# biofeedback_2560_3V.net
KiCad netlist of a schematic drawn in EAGLE
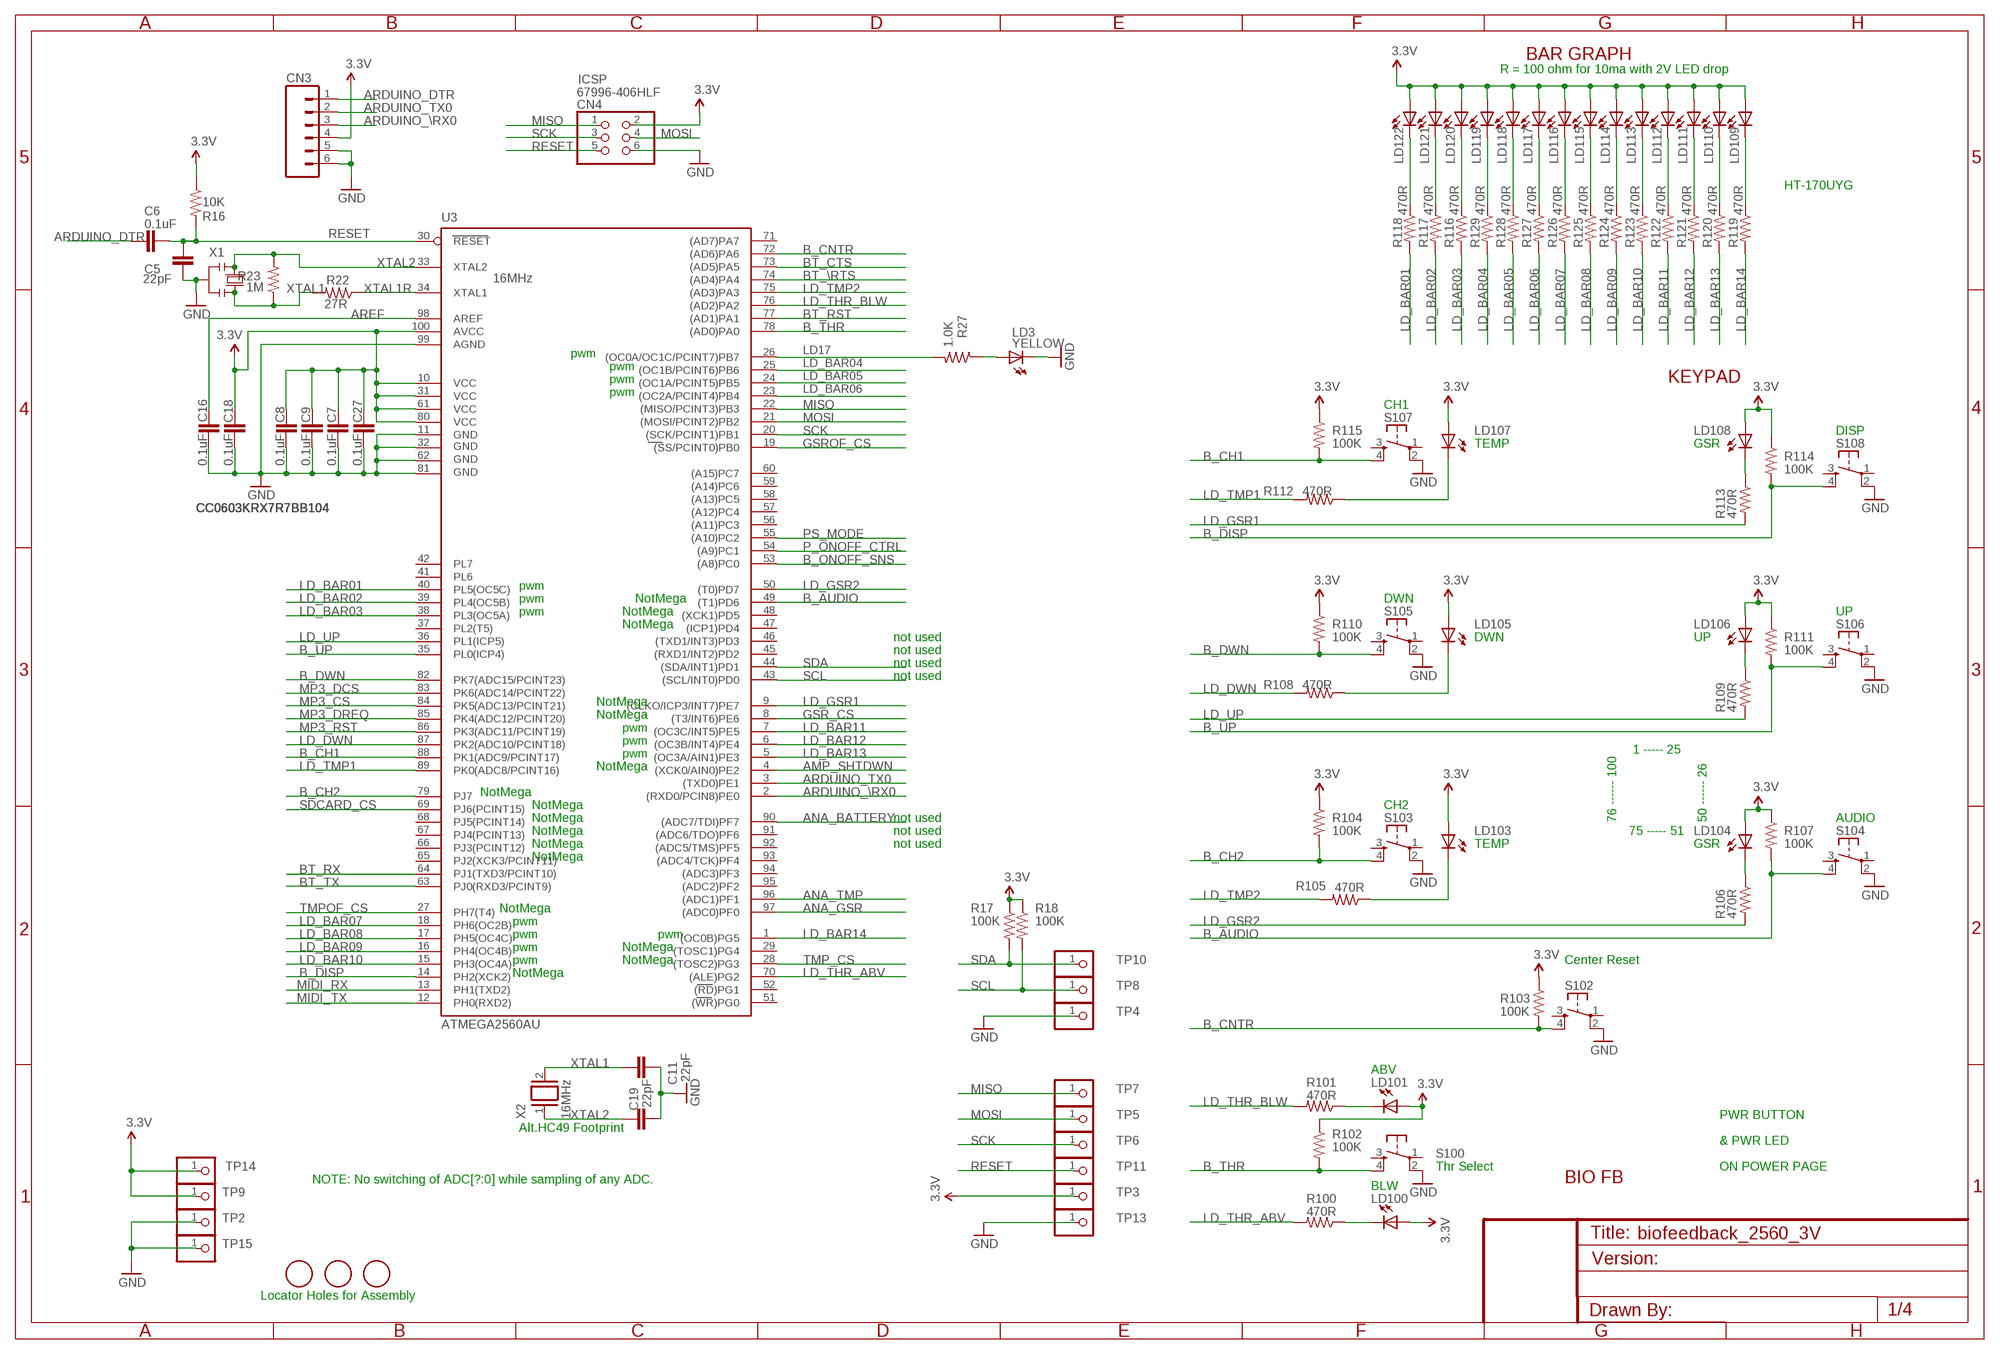
[diagram p0: schematic, sheet 1]
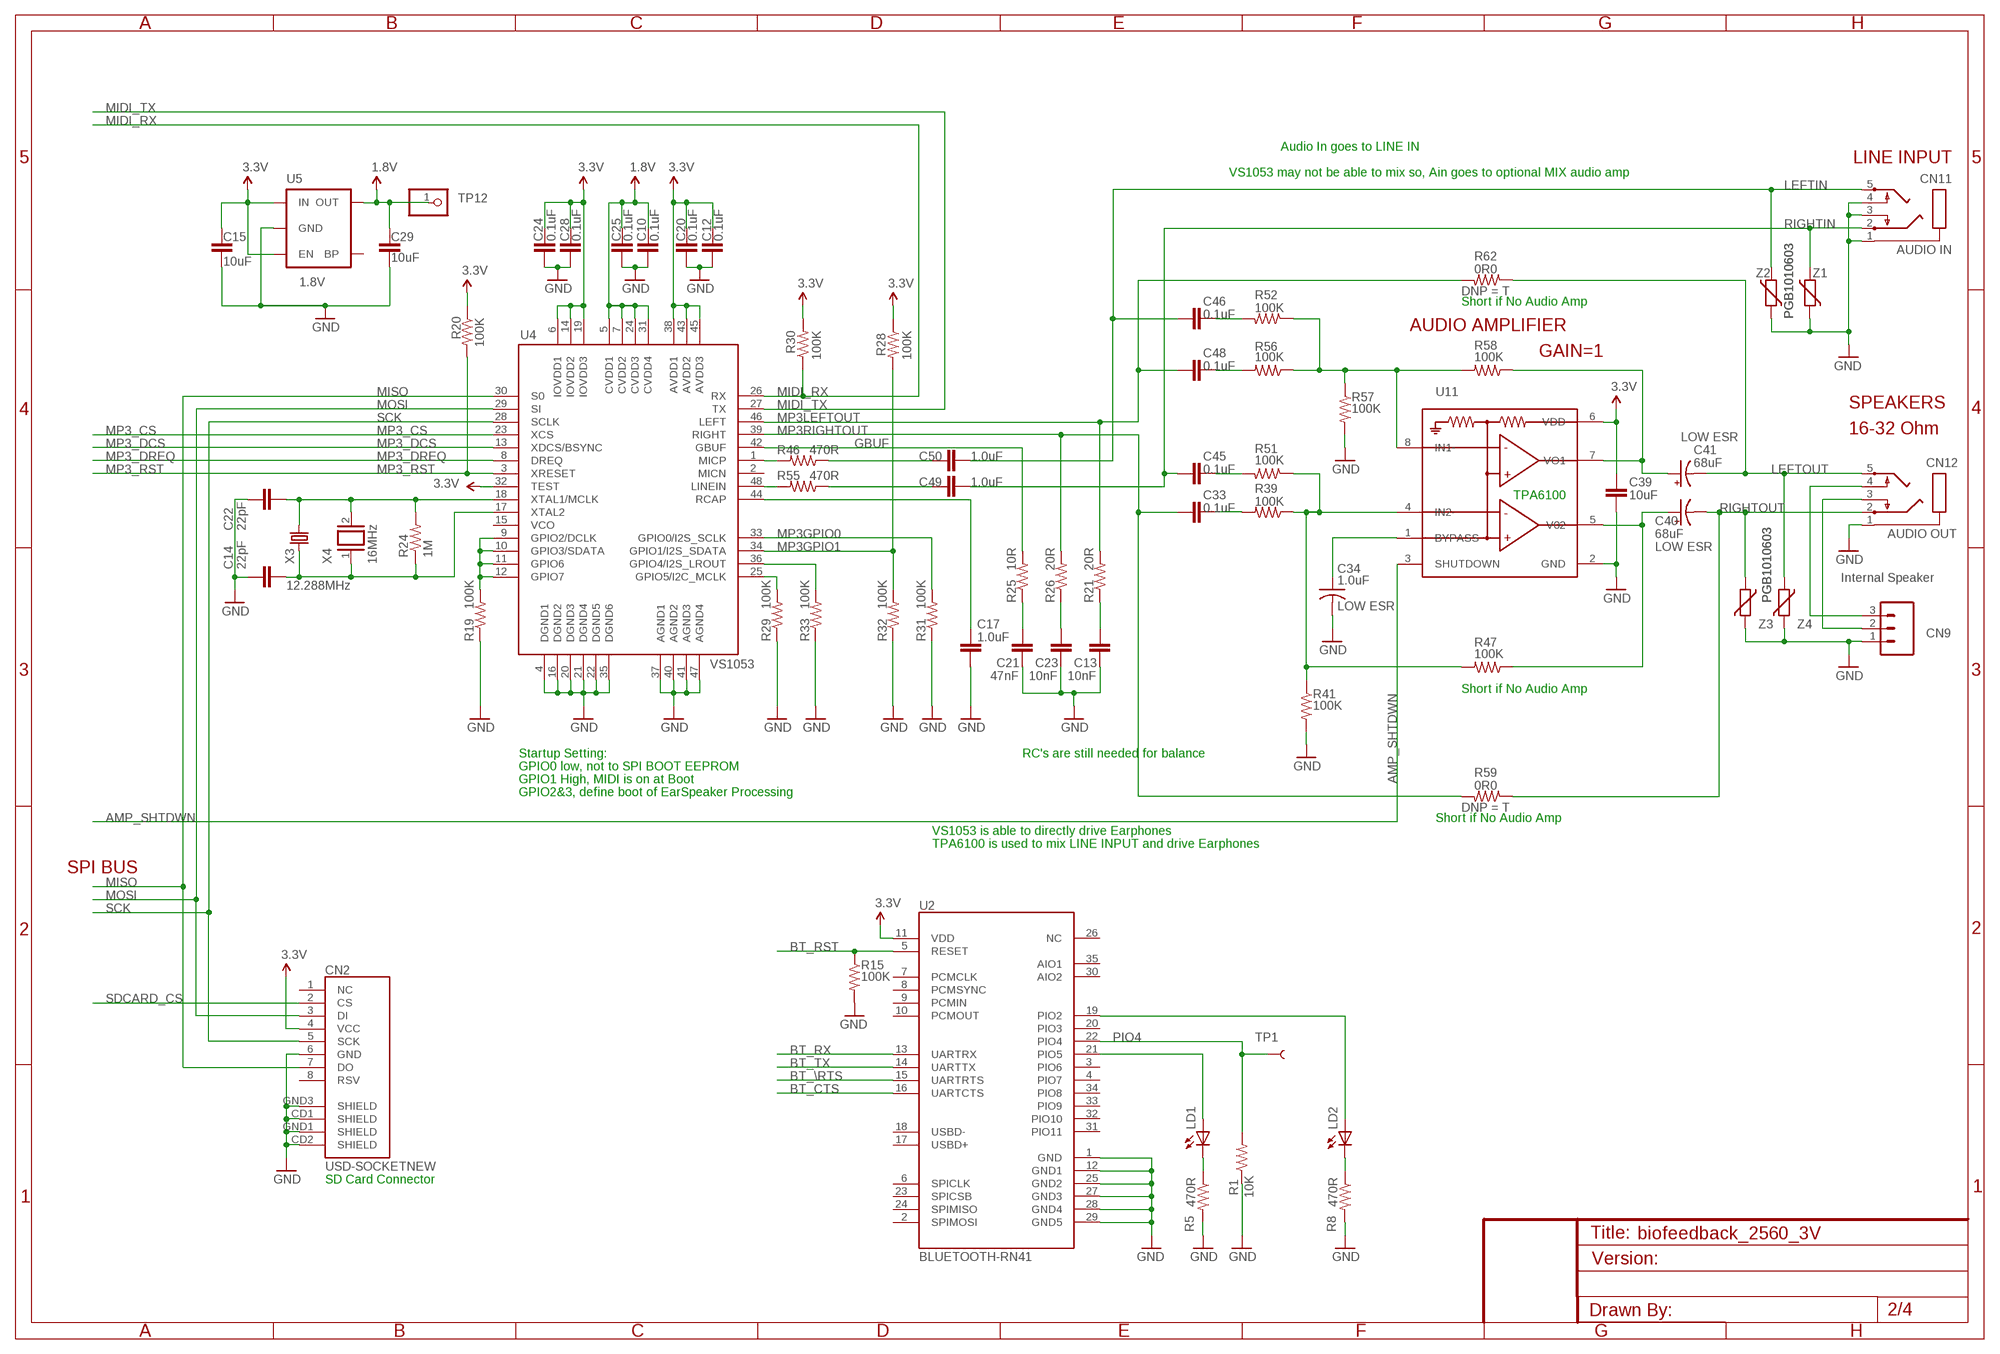
[diagram p1: schematic, sheet 2]
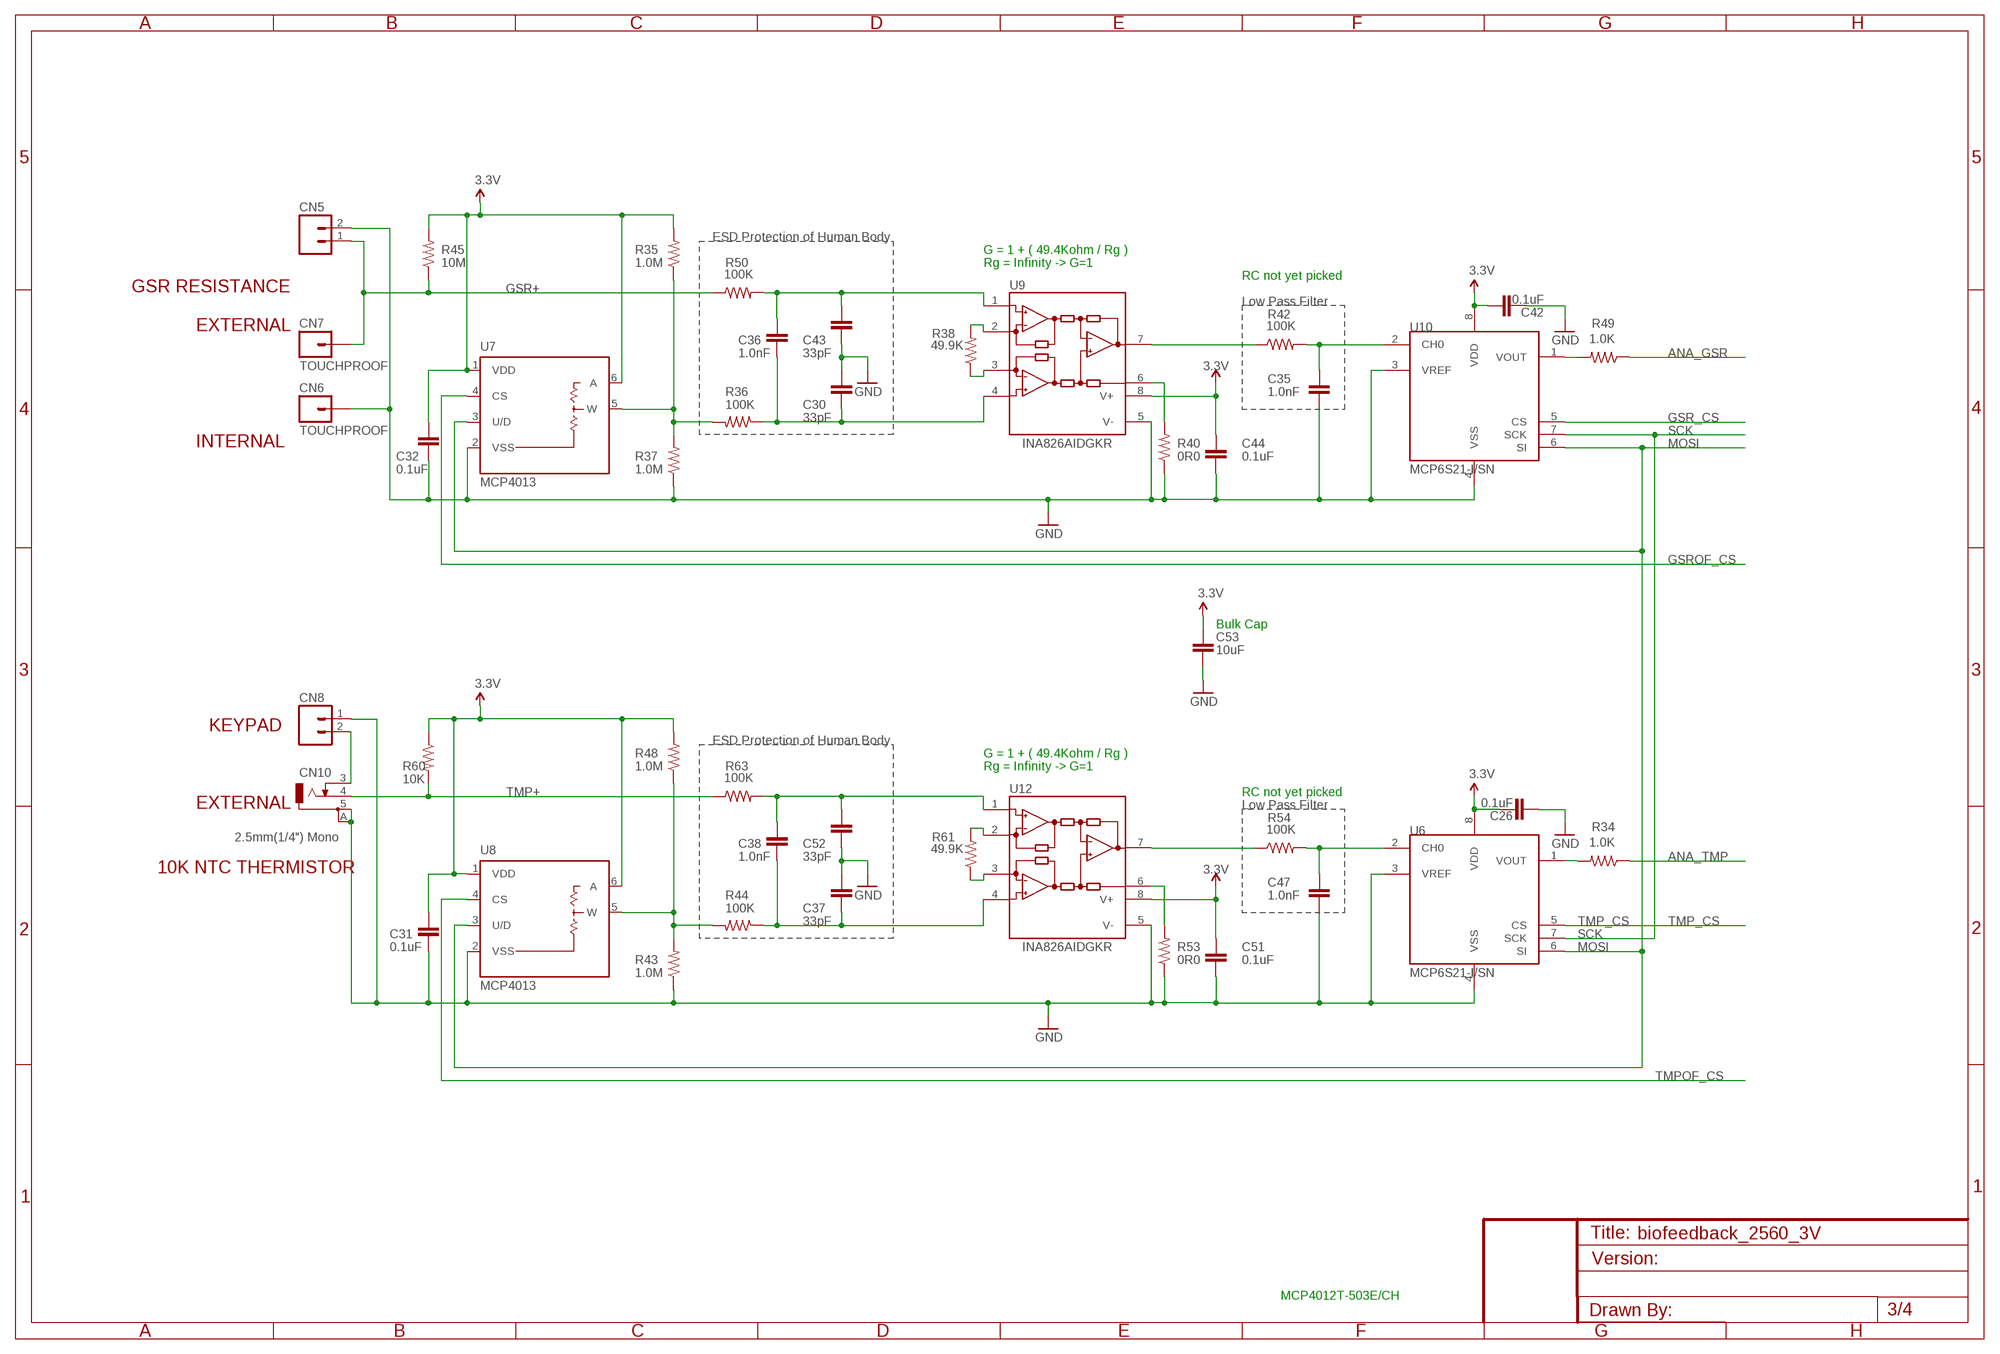
[diagram p2: schematic, sheet 3]
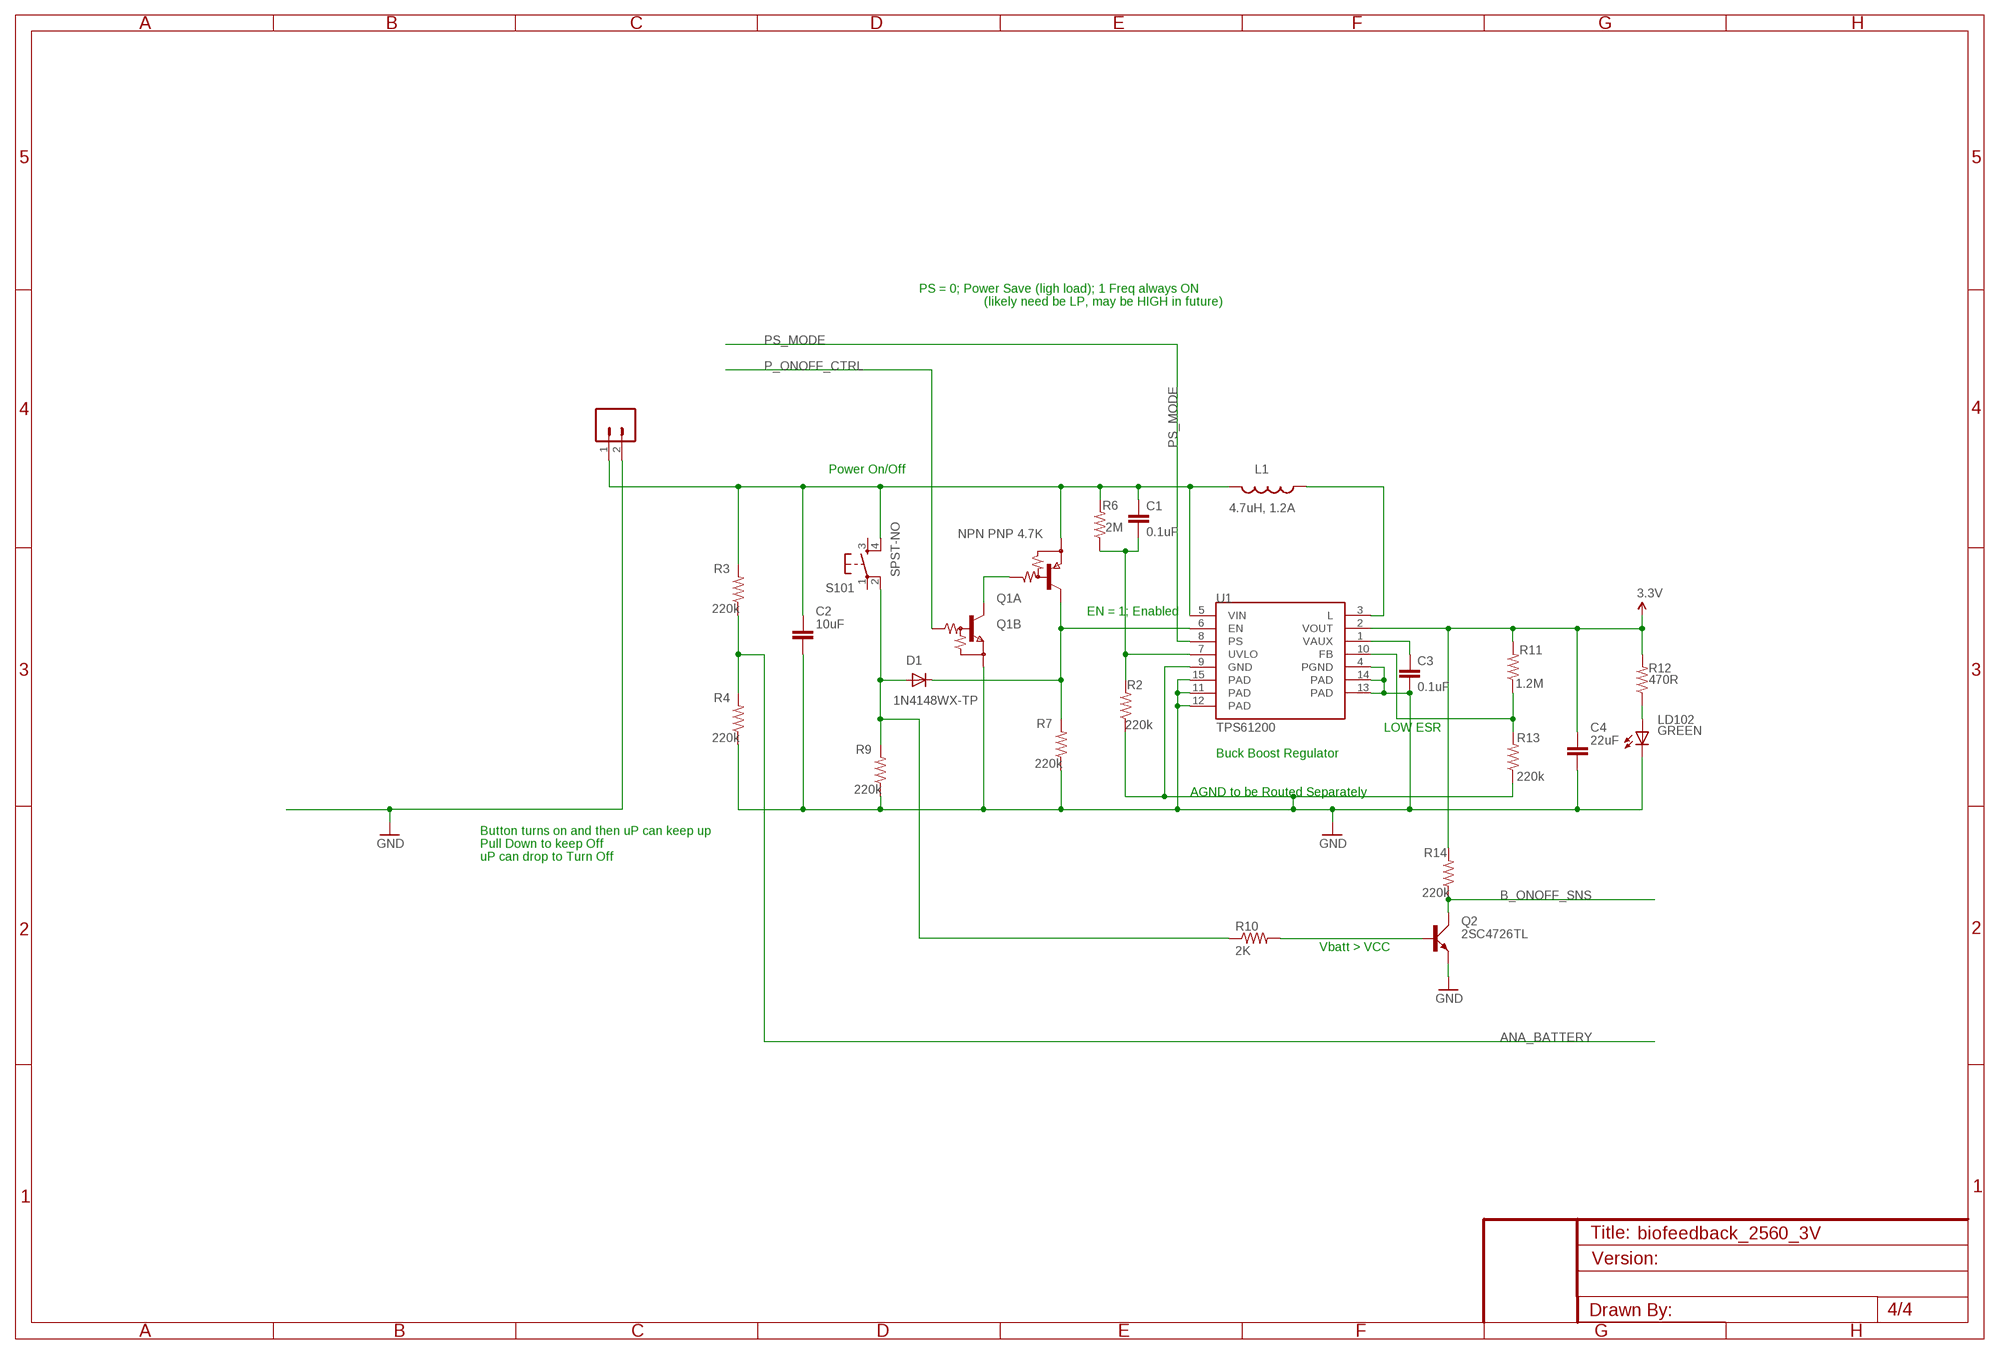
[diagram p3: schematic, sheet 4]

(export (version "E")
  (design (tool "Eeschema 10.0.6"))
  (components
    (comp (ref "C5")
      (value "22pF")
      (footprint "eagle-import:C0603")
      (fields (field (name "PARTNO") "GRM0335C1E220JD01D"))
      (libsource (lib "eagle-import") (part "resistor_C-EUC0603"))
    )
    (comp (ref "C6")
      (value "0.1uF")
      (footprint "eagle-import:C0603")
      (fields (field (name "PARTNO") "CC0603KRX7R7BB104"))
      (libsource (lib "eagle-import") (part "resistor_C-EUC0603"))
    )
    (comp (ref "C7")
      (value "0.1uF")
      (footprint "eagle-import:C0603")
      (fields (field (name "PARTNO") "CC0603KRX7R7BB104"))
      (libsource (lib "eagle-import") (part "resistor_C-EUC0603"))
    )
    (comp (ref "C8")
      (value "0.1uF")
      (footprint "eagle-import:C0603")
      (fields (field (name "PARTNO") "CC0603KRX7R7BB104"))
      (libsource (lib "eagle-import") (part "resistor_C-EUC0603"))
    )
    (comp (ref "C9")
      (value "0.1uF")
      (footprint "eagle-import:C0603")
      (fields (field (name "PARTNO") "CC0603KRX7R7BB104"))
      (libsource (lib "eagle-import") (part "resistor_C-EUC0603"))
    )
    (comp (ref "C11")
      (value "22pF")
      (footprint "eagle-import:C0603")
      (fields (field (name "PARTNO") "GRM0335C1E220JD01D"))
      (libsource (lib "eagle-import") (part "resistor_C-EUC0603"))
    )
    (comp (ref "C16")
      (value "0.1uF")
      (footprint "eagle-import:C0603")
      (fields (field (name "PARTNO") "CC0603KRX7R7BB104"))
      (libsource (lib "eagle-import") (part "resistor_C-EUC0603"))
    )
    (comp (ref "C18")
      (value "0.1uF")
      (footprint "eagle-import:C0603")
      (fields (field (name "PARTNO") "CC0603KRX7R7BB104"))
      (libsource (lib "eagle-import") (part "resistor_C-EUC0603"))
    )
    (comp (ref "C19")
      (value "22pF")
      (footprint "eagle-import:C0603")
      (fields (field (name "PARTNO") "GRM0335C1E220JD01D"))
      (libsource (lib "eagle-import") (part "resistor_C-EUC0603"))
    )
    (comp (ref "C27")
      (value "0.1uF")
      (footprint "eagle-import:C0603")
      (fields (field (name "PARTNO") "CC0603KRX7R7BB104"))
      (libsource (lib "eagle-import") (part "resistor_C-EUC0603"))
    )
    (comp (ref "CN3")
      (value "NSTUFF")
      (footprint "eagle-import:1X06")
      (fields (field (name "PARTNO") "640456-6"))
      (libsource (lib "eagle-import") (part "M06SIP"))
    )
    (comp (ref "CN4")
      (value "ICSP")
      (footprint "eagle-import:2X03")
      (fields (field (name "PARTNO") "67996-406HLF"))
      (libsource (lib "eagle-import") (part "PINHD-2X3"))
    )
    (comp (ref "LD3")
      (value "YELLOW")
      (footprint "eagle-import:CHIP-LED0805")
      (fields (field (name "PARTNO") "APT2012YC"))
      (libsource (lib "eagle-import") (part "LEDCHIP-LED0805"))
    )
    (comp (ref "LD100")
      (value "GREEN")
      (footprint "eagle-import:CHIP-LED0805")
      (fields (field (name "PARTNO") "LG R971-KN-1-0-20-R18"))
      (libsource (lib "eagle-import") (part "LEDCHIP-LED0805"))
    )
    (comp (ref "LD101")
      (value "GREEN")
      (footprint "eagle-import:CHIP-LED0805")
      (fields (field (name "PARTNO") "LG R971-KN-1-0-20-R18"))
      (libsource (lib "eagle-import") (part "LEDCHIP-LED0805"))
    )
    (comp (ref "LD103")
      (value "GREEN")
      (footprint "eagle-import:CHIP-LED0805")
      (fields (field (name "PARTNO") "LG R971-KN-1-0-20-R18"))
      (libsource (lib "eagle-import") (part "LEDCHIP-LED0805"))
    )
    (comp (ref "LD104")
      (value "GREEN")
      (footprint "eagle-import:CHIP-LED0805")
      (fields (field (name "PARTNO") "LG R971-KN-1-0-20-R18"))
      (libsource (lib "eagle-import") (part "LEDCHIP-LED0805"))
    )
    (comp (ref "LD105")
      (value "GREEN")
      (footprint "eagle-import:CHIP-LED0805")
      (fields (field (name "PARTNO") "LG R971-KN-1-0-20-R18"))
      (libsource (lib "eagle-import") (part "LEDCHIP-LED0805"))
    )
    (comp (ref "LD106")
      (value "GREEN")
      (footprint "eagle-import:CHIP-LED0805")
      (fields (field (name "PARTNO") "LG R971-KN-1-0-20-R18"))
      (libsource (lib "eagle-import") (part "LEDCHIP-LED0805"))
    )
    (comp (ref "LD107")
      (value "GREEN")
      (footprint "eagle-import:CHIP-LED0805")
      (fields (field (name "PARTNO") "LG R971-KN-1-0-20-R18"))
      (libsource (lib "eagle-import") (part "LEDCHIP-LED0805"))
    )
    (comp (ref "LD108")
      (value "GREEN")
      (footprint "eagle-import:CHIP-LED0805")
      (fields (field (name "PARTNO") "LG R971-KN-1-0-20-R18"))
      (libsource (lib "eagle-import") (part "LEDCHIP-LED0805"))
    )
    (comp (ref "LD109")
      (value "GREEN")
      (footprint "eagle-import:CHIP-LED0805")
      (fields (field (name "PARTNO") "LG R971-KN-1-0-20-R18"))
      (libsource (lib "eagle-import") (part "LEDCHIP-LED0805"))
    )
    (comp (ref "LD110")
      (value "GREEN")
      (footprint "eagle-import:CHIP-LED0805")
      (fields (field (name "PARTNO") "LG R971-KN-1-0-20-R18"))
      (libsource (lib "eagle-import") (part "LEDCHIP-LED0805"))
    )
    (comp (ref "LD111")
      (value "GREEN")
      (footprint "eagle-import:CHIP-LED0805")
      (fields (field (name "PARTNO") "LG R971-KN-1-0-20-R18"))
      (libsource (lib "eagle-import") (part "LEDCHIP-LED0805"))
    )
    (comp (ref "LD112")
      (value "GREEN")
      (footprint "eagle-import:CHIP-LED0805")
      (fields (field (name "PARTNO") "LG R971-KN-1-0-20-R18"))
      (libsource (lib "eagle-import") (part "LEDCHIP-LED0805"))
    )
    (comp (ref "LD113")
      (value "GREEN")
      (footprint "eagle-import:CHIP-LED0805")
      (fields (field (name "PARTNO") "LG R971-KN-1-0-20-R18"))
      (libsource (lib "eagle-import") (part "LEDCHIP-LED0805"))
    )
    (comp (ref "LD114")
      (value "GREEN")
      (footprint "eagle-import:CHIP-LED0805")
      (fields (field (name "PARTNO") "LG R971-KN-1-0-20-R18"))
      (libsource (lib "eagle-import") (part "LEDCHIP-LED0805"))
    )
    (comp (ref "LD115")
      (value "GREEN")
      (footprint "eagle-import:CHIP-LED0805")
      (fields (field (name "PARTNO") "LG R971-KN-1-0-20-R18"))
      (libsource (lib "eagle-import") (part "LEDCHIP-LED0805"))
    )
    (comp (ref "LD116")
      (value "GREEN")
      (footprint "eagle-import:CHIP-LED0805")
      (fields (field (name "PARTNO") "LG R971-KN-1-0-20-R18"))
      (libsource (lib "eagle-import") (part "LEDCHIP-LED0805"))
    )
    (comp (ref "LD117")
      (value "GREEN")
      (footprint "eagle-import:CHIP-LED0805")
      (fields (field (name "PARTNO") "LG R971-KN-1-0-20-R18"))
      (libsource (lib "eagle-import") (part "LEDCHIP-LED0805"))
    )
    (comp (ref "LD118")
      (value "GREEN")
      (footprint "eagle-import:CHIP-LED0805")
      (fields (field (name "PARTNO") "LG R971-KN-1-0-20-R18"))
      (libsource (lib "eagle-import") (part "LEDCHIP-LED0805"))
    )
    (comp (ref "LD119")
      (value "GREEN")
      (footprint "eagle-import:CHIP-LED0805")
      (fields (field (name "PARTNO") "LG R971-KN-1-0-20-R18"))
      (libsource (lib "eagle-import") (part "LEDCHIP-LED0805"))
    )
    (comp (ref "LD120")
      (value "GREEN")
      (footprint "eagle-import:CHIP-LED0805")
      (fields (field (name "PARTNO") "LG R971-KN-1-0-20-R18"))
      (libsource (lib "eagle-import") (part "LEDCHIP-LED0805"))
    )
    (comp (ref "LD121")
      (value "GREEN")
      (footprint "eagle-import:CHIP-LED0805")
      (fields (field (name "PARTNO") "LG R971-KN-1-0-20-R18"))
      (libsource (lib "eagle-import") (part "LEDCHIP-LED0805"))
    )
    (comp (ref "LD122")
      (value "GREEN")
      (footprint "eagle-import:CHIP-LED0805")
      (fields (field (name "PARTNO") "LG R971-KN-1-0-20-R18"))
      (libsource (lib "eagle-import") (part "LEDCHIP-LED0805"))
    )
    (comp (ref "MN1")
      (value "FIDUCIALMOUNT")
      (footprint "eagle-import:FIDUCIA-MOUNT")
      (libsource (lib "eagle-import") (part "FIDUCIALMOUNT"))
    )
    (comp (ref "MN2")
      (value "FIDUCIALMOUNT")
      (footprint "eagle-import:FIDUCIA-MOUNT")
      (libsource (lib "eagle-import") (part "FIDUCIALMOUNT"))
    )
    (comp (ref "MN3")
      (value "FIDUCIALMOUNT")
      (footprint "eagle-import:FIDUCIA-MOUNT")
      (libsource (lib "eagle-import") (part "FIDUCIALMOUNT"))
    )
    (comp (ref "R16")
      (value "10K")
      (footprint "eagle-import:R0603")
      (fields (field (name "PARTNO") "RC0603JR-0710KL"))
      (libsource (lib "eagle-import") (part "R-US_R0603"))
    )
    (comp (ref "R17")
      (value "100K")
      (footprint "eagle-import:R0603")
      (fields (field (name "PARTNO") "RC0603JR-07100KL"))
      (libsource (lib "eagle-import") (part "R-US_R0603"))
    )
    (comp (ref "R18")
      (value "100K")
      (footprint "eagle-import:R0603")
      (fields (field (name "PARTNO") "RC0603JR-07100KL"))
      (libsource (lib "eagle-import") (part "R-US_R0603"))
    )
    (comp (ref "R22")
      (value "27R")
      (footprint "eagle-import:R0603")
      (fields (field (name "PARTNO") "ERJ-3EKF27R0V"))
      (libsource (lib "eagle-import") (part "R-US_R0603"))
    )
    (comp (ref "R23")
      (value "1M")
      (footprint "eagle-import:R0603")
      (fields (field (name "PARTNO") "RC0603JR-071ML"))
      (libsource (lib "eagle-import") (part "R-US_R0603"))
    )
    (comp (ref "R27")
      (value "1.0K")
      (footprint "eagle-import:R0603")
      (fields (field (name "PARTNO") "RC0603JR-071KL"))
      (libsource (lib "eagle-import") (part "R-US_R0603"))
    )
    (comp (ref "R100")
      (value "470R")
      (footprint "eagle-import:R0603")
      (fields (field (name "PARTNO") "RC0603JR-07470RL"))
      (libsource (lib "eagle-import") (part "R-US_R0603"))
    )
    (comp (ref "R101")
      (value "470R")
      (footprint "eagle-import:R0603")
      (fields (field (name "PARTNO") "RC0603JR-07470RL"))
      (libsource (lib "eagle-import") (part "R-US_R0603"))
    )
    (comp (ref "R102")
      (value "100K")
      (footprint "eagle-import:R0603")
      (fields (field (name "PARTNO") "RC0603JR-07100KL"))
      (libsource (lib "eagle-import") (part "R-US_R0603"))
    )
    (comp (ref "R103")
      (value "100K")
      (footprint "eagle-import:R0603")
      (fields (field (name "PARTNO") "RC0603JR-07100KL"))
      (libsource (lib "eagle-import") (part "R-US_R0603"))
    )
    (comp (ref "R104")
      (value "100K")
      (footprint "eagle-import:R0603")
      (fields (field (name "PARTNO") "RC0603JR-07100KL"))
      (libsource (lib "eagle-import") (part "R-US_R0603"))
    )
    (comp (ref "R105")
      (value "470R")
      (footprint "eagle-import:R0603")
      (fields (field (name "PARTNO") "RC0603JR-07470RL"))
      (libsource (lib "eagle-import") (part "R-US_R0603"))
    )
    (comp (ref "R106")
      (value "470R")
      (footprint "eagle-import:R0603")
      (fields (field (name "PARTNO") "RC0603JR-07470RL"))
      (libsource (lib "eagle-import") (part "R-US_R0603"))
    )
    (comp (ref "R107")
      (value "100K")
      (footprint "eagle-import:R0603")
      (fields (field (name "PARTNO") "RC0603JR-07100KL"))
      (libsource (lib "eagle-import") (part "R-US_R0603"))
    )
    (comp (ref "R108")
      (value "470R")
      (footprint "eagle-import:R0603")
      (fields (field (name "PARTNO") "RC0603JR-07470RL"))
      (libsource (lib "eagle-import") (part "R-US_R0603"))
    )
    (comp (ref "R109")
      (value "470R")
      (footprint "eagle-import:R0603")
      (fields (field (name "PARTNO") "RC0603JR-07470RL"))
      (libsource (lib "eagle-import") (part "R-US_R0603"))
    )
    (comp (ref "R110")
      (value "100K")
      (footprint "eagle-import:R0603")
      (fields (field (name "PARTNO") "RC0603JR-07100KL"))
      (libsource (lib "eagle-import") (part "R-US_R0603"))
    )
    (comp (ref "R111")
      (value "100K")
      (footprint "eagle-import:R0603")
      (fields (field (name "PARTNO") "RC0603JR-07100KL"))
      (libsource (lib "eagle-import") (part "R-US_R0603"))
    )
    (comp (ref "R112")
      (value "470R")
      (footprint "eagle-import:R0603")
      (fields (field (name "PARTNO") "RC0603JR-07470RL"))
      (libsource (lib "eagle-import") (part "R-US_R0603"))
    )
    (comp (ref "R113")
      (value "470R")
      (footprint "eagle-import:R0603")
      (fields (field (name "PARTNO") "RC0603JR-07470RL"))
      (libsource (lib "eagle-import") (part "R-US_R0603"))
    )
    (comp (ref "R114")
      (value "100K")
      (footprint "eagle-import:R0603")
      (fields (field (name "PARTNO") "RC0603JR-07100KL"))
      (libsource (lib "eagle-import") (part "R-US_R0603"))
    )
    (comp (ref "R115")
      (value "100K")
      (footprint "eagle-import:R0603")
      (fields (field (name "PARTNO") "RC0603JR-07100KL"))
      (libsource (lib "eagle-import") (part "R-US_R0603"))
    )
    (comp (ref "R116")
      (value "470R")
      (footprint "eagle-import:R0603")
      (fields (field (name "PARTNO") "RC0603JR-07470RL"))
      (libsource (lib "eagle-import") (part "R-US_R0603"))
    )
    (comp (ref "R117")
      (value "470R")
      (footprint "eagle-import:R0603")
      (fields (field (name "PARTNO") "RC0603JR-07470RL"))
      (libsource (lib "eagle-import") (part "R-US_R0603"))
    )
    (comp (ref "R118")
      (value "470R")
      (footprint "eagle-import:R0603")
      (fields (field (name "PARTNO") "RC0603JR-07470RL"))
      (libsource (lib "eagle-import") (part "R-US_R0603"))
    )
    (comp (ref "R119")
      (value "470R")
      (footprint "eagle-import:R0603")
      (fields (field (name "PARTNO") "RC0603JR-07470RL"))
      (libsource (lib "eagle-import") (part "R-US_R0603"))
    )
    (comp (ref "R120")
      (value "470R")
      (footprint "eagle-import:R0603")
      (fields (field (name "PARTNO") "RC0603JR-07470RL"))
      (libsource (lib "eagle-import") (part "R-US_R0603"))
    )
    (comp (ref "R121")
      (value "470R")
      (footprint "eagle-import:R0603")
      (fields (field (name "PARTNO") "RC0603JR-07470RL"))
      (libsource (lib "eagle-import") (part "R-US_R0603"))
    )
    (comp (ref "R122")
      (value "470R")
      (footprint "eagle-import:R0603")
      (fields (field (name "PARTNO") "RC0603JR-07470RL"))
      (libsource (lib "eagle-import") (part "R-US_R0603"))
    )
    (comp (ref "R123")
      (value "470R")
      (footprint "eagle-import:R0603")
      (fields (field (name "PARTNO") "RC0603JR-07470RL"))
      (libsource (lib "eagle-import") (part "R-US_R0603"))
    )
    (comp (ref "R124")
      (value "470R")
      (footprint "eagle-import:R0603")
      (fields (field (name "PARTNO") "RC0603JR-07470RL"))
      (libsource (lib "eagle-import") (part "R-US_R0603"))
    )
    (comp (ref "R125")
      (value "470R")
      (footprint "eagle-import:R0603")
      (fields (field (name "PARTNO") "RC0603JR-07470RL"))
      (libsource (lib "eagle-import") (part "R-US_R0603"))
    )
    (comp (ref "R126")
      (value "470R")
      (footprint "eagle-import:R0603")
      (fields (field (name "PARTNO") "RC0603JR-07470RL"))
      (libsource (lib "eagle-import") (part "R-US_R0603"))
    )
    (comp (ref "R127")
      (value "470R")
      (footprint "eagle-import:R0603")
      (fields (field (name "PARTNO") "RC0603JR-07470RL"))
      (libsource (lib "eagle-import") (part "R-US_R0603"))
    )
    (comp (ref "R128")
      (value "470R")
      (footprint "eagle-import:R0603")
      (fields (field (name "PARTNO") "RC0603JR-07470RL"))
      (libsource (lib "eagle-import") (part "R-US_R0603"))
    )
    (comp (ref "R129")
      (value "470R")
      (footprint "eagle-import:R0603")
      (fields (field (name "PARTNO") "RC0603JR-07470RL"))
      (libsource (lib "eagle-import") (part "R-US_R0603"))
    )
    (comp (ref "S100")
      (value "SPST-NO")
      (footprint "eagle-import:TACTILE_SWITCH_SMD_6MM_SQ")
      (fields (field (name "PARTNO") "TL3301PF160QG"))
      (libsource (lib "eagle-import") (part "TAC_SWITCH"))
    )
    (comp (ref "S102")
      (value "SPST-NO")
      (footprint "eagle-import:TACTILE_SWITCH_SMD_6MM_SQ")
      (fields (field (name "PARTNO") "TL3301PF160QG"))
      (libsource (lib "eagle-import") (part "TAC_SWITCH"))
    )
    (comp (ref "S103")
      (value "SPST-NO")
      (footprint "eagle-import:TACTILE_SWITCH_SMD_6MM_SQ")
      (fields (field (name "PARTNO") "TL3301PF160QG"))
      (libsource (lib "eagle-import") (part "TAC_SWITCH"))
    )
    (comp (ref "S104")
      (value "SPST-NO")
      (footprint "eagle-import:TACTILE_SWITCH_SMD_6MM_SQ")
      (fields (field (name "PARTNO") "TL3301PF160QG"))
      (libsource (lib "eagle-import") (part "TAC_SWITCH"))
    )
    (comp (ref "S105")
      (value "SPST-NO")
      (footprint "eagle-import:TACTILE_SWITCH_SMD_6MM_SQ")
      (fields (field (name "PARTNO") "TL3301PF160QG"))
      (libsource (lib "eagle-import") (part "TAC_SWITCH"))
    )
    (comp (ref "S106")
      (value "SPST-NO")
      (footprint "eagle-import:TACTILE_SWITCH_SMD_6MM_SQ")
      (fields (field (name "PARTNO") "TL3301PF160QG"))
      (libsource (lib "eagle-import") (part "TAC_SWITCH"))
    )
    (comp (ref "S107")
      (value "SPST-NO")
      (footprint "eagle-import:TACTILE_SWITCH_SMD_6MM_SQ")
      (fields (field (name "PARTNO") "TL3301PF160QG"))
      (libsource (lib "eagle-import") (part "TAC_SWITCH"))
    )
    (comp (ref "S108")
      (value "SPST-NO")
      (footprint "eagle-import:TACTILE_SWITCH_SMD_6MM_SQ")
      (fields (field (name "PARTNO") "TL3301PF160QG"))
      (libsource (lib "eagle-import") (part "TAC_SWITCH"))
    )
    (comp (ref "TP2")
      (value "NSTUFF")
      (footprint "eagle-import:1X01")
      (libsource (lib "eagle-import") (part "PINHD-1X1"))
    )
    (comp (ref "TP3")
      (value "NSTUFF")
      (footprint "eagle-import:1X01")
      (libsource (lib "eagle-import") (part "PINHD-1X1"))
    )
    (comp (ref "TP4")
      (value "NSTUFF")
      (footprint "eagle-import:1X01")
      (libsource (lib "eagle-import") (part "PINHD-1X1"))
    )
    (comp (ref "TP5")
      (value "NSTUFF")
      (footprint "eagle-import:1X01")
      (libsource (lib "eagle-import") (part "PINHD-1X1"))
    )
    (comp (ref "TP6")
      (value "NSTUFF")
      (footprint "eagle-import:1X01")
      (libsource (lib "eagle-import") (part "PINHD-1X1"))
    )
    (comp (ref "TP7")
      (value "NSTUFF")
      (footprint "eagle-import:1X01")
      (libsource (lib "eagle-import") (part "PINHD-1X1"))
    )
    (comp (ref "TP8")
      (value "NSTUFF")
      (footprint "eagle-import:1X01")
      (libsource (lib "eagle-import") (part "PINHD-1X1"))
    )
    (comp (ref "TP9")
      (value "NSTUFF")
      (footprint "eagle-import:1X01")
      (libsource (lib "eagle-import") (part "PINHD-1X1"))
    )
    (comp (ref "TP10")
      (value "NSTUFF")
      (footprint "eagle-import:1X01")
      (libsource (lib "eagle-import") (part "PINHD-1X1"))
    )
    (comp (ref "TP11")
      (value "NSTUFF")
      (footprint "eagle-import:1X01")
      (libsource (lib "eagle-import") (part "PINHD-1X1"))
    )
    (comp (ref "TP13")
      (value "NSTUFF")
      (footprint "eagle-import:1X01")
      (libsource (lib "eagle-import") (part "PINHD-1X1"))
    )
    (comp (ref "TP14")
      (value "NSTUFF")
      (footprint "eagle-import:1X01")
      (libsource (lib "eagle-import") (part "PINHD-1X1"))
    )
    (comp (ref "TP15")
      (value "NSTUFF")
      (footprint "eagle-import:1X01")
      (libsource (lib "eagle-import") (part "PINHD-1X1"))
    )
    (comp (ref "U3")
      (value "ATMEGA2560AU")
      (footprint "eagle-import:TQFP100")
      (fields (field (name "PARTNO") "ATMEGA2560-16AU"))
      (libsource (lib "eagle-import") (part "ATMEGA2560AU"))
    )
    (comp (ref "X1")
      (value "16MHz")
      (footprint "eagle-import:RESONATOR")
      (fields (field (name "PARTNO") "AWSCR-16.00CV-T"))
      (libsource (lib "eagle-import") (part "RESONATORMU"))
    )
    (comp (ref "X2")
      (value "16MHz")
      (footprint "eagle-import:QS")
      (fields (field (name "PARTNO") "ATS16B"))
      (libsource (lib "eagle-import") (part "special_XTAL/S"))
    )
    (comp (ref "C1")
      (value "0.1uF")
      (footprint "eagle-import:C0603")
      (fields (field (name "PARTNO") "CC0603KRX7R7BB104"))
      (libsource (lib "eagle-import") (part "resistor_C-EUC0603"))
    )
    (comp (ref "C2")
      (value "10uF")
      (footprint "eagle-import:C0603")
      (fields (field (name "PARTNO") "C1608X5R1A106M"))
      (libsource (lib "eagle-import") (part "resistor_C-EUC0603"))
    )
    (comp (ref "C3")
      (value "0.1uF")
      (footprint "eagle-import:C0603")
      (fields (field (name "PARTNO") "CC0603KRX7R7BB104"))
      (libsource (lib "eagle-import") (part "resistor_C-EUC0603"))
    )
    (comp (ref "C4")
      (value "22uF")
      (footprint "eagle-import:C0603")
      (fields (field (name "PARTNO") "250R14W224KV4T"))
      (libsource (lib "eagle-import") (part "resistor_C-EUC0603"))
    )
    (comp (ref "CN1")
      (value "CONN HEADER PH TOP 2POS 2MM")
      (footprint "eagle-import:1X02")
      (fields (field (name "PARTNO") "B2B-PH-K-S(LF)(SN)"))
      (libsource (lib "eagle-import") (part "M02PTH"))
    )
    (comp (ref "D1")
      (value "1N4148WX-TP")
      (footprint "eagle-import:SOD323-R")
      (libsource (lib "eagle-import") (part "DIODE-SOD323-R"))
    )
    (comp (ref "L1")
      (value "4.7uH, 1.2A")
      (footprint "eagle-import:CDRH2D09")
      (fields (field (name "PARTNO") "CDRH2D09NP-4R7MC"))
      (libsource (lib "eagle-import") (part "INDUCTOR."))
    )
    (comp (ref "LD102")
      (value "GREEN")
      (footprint "eagle-import:CHIP-LED0805")
      (fields (field (name "PARTNO") "LG R971-KN-1-0-20-R18"))
      (libsource (lib "eagle-import") (part "LEDCHIP-LED0805"))
    )
    (comp (ref "Q1")
      (value "NPN PNP 4.7K")
      (footprint "eagle-import:SOT-23-6")
      (fields (field (name "PARTNO") "DMG264060R"))
      (libsource (lib "eagle-import") (part "NPN_PNPSM8"))
    )
    (comp (ref "Q2")
      (value "2SC4726TL")
      (footprint "eagle-import:EMT3")
      (fields (field (name "PARTNO") "MMBT3904TT1G"))
      (libsource (lib "eagle-import") (part "2SC4726TL"))
    )
    (comp (ref "R2")
      (value "220k")
      (footprint "eagle-import:R0603")
      (fields (field (name "PARTNO") "RC0603JR-07220KL"))
      (libsource (lib "eagle-import") (part "R-US_R0603"))
    )
    (comp (ref "R3")
      (value "220k")
      (footprint "eagle-import:R0603")
      (fields (field (name "PARTNO") "RC0603JR-07220KL"))
      (libsource (lib "eagle-import") (part "R-US_R0603"))
    )
    (comp (ref "R4")
      (value "220k")
      (footprint "eagle-import:R0603")
      (fields (field (name "PARTNO") "RC0603JR-07220KL"))
      (libsource (lib "eagle-import") (part "R-US_R0603"))
    )
    (comp (ref "R6")
      (value "2M")
      (footprint "eagle-import:R0603")
      (fields (field (name "PARTNO") "RC0603JR-072ML"))
      (libsource (lib "eagle-import") (part "R-US_R0603"))
    )
    (comp (ref "R7")
      (value "220k")
      (footprint "eagle-import:R0603")
      (fields (field (name "PARTNO") "RC0603JR-07220KL"))
      (libsource (lib "eagle-import") (part "R-US_R0603"))
    )
    (comp (ref "R9")
      (value "220k")
      (footprint "eagle-import:R0603")
      (fields (field (name "PARTNO") "RC0603JR-07220KL"))
      (libsource (lib "eagle-import") (part "R-US_R0603"))
    )
    (comp (ref "R10")
      (value "2K")
      (footprint "eagle-import:R0603")
      (fields (field (name "PARTNO") "RC0603JR-072KL"))
      (libsource (lib "eagle-import") (part "R-US_R0603"))
    )
    (comp (ref "R11")
      (value "1.2M")
      (footprint "eagle-import:R0603")
      (fields (field (name "PARTNO") "CRCW04021M20FKED"))
      (libsource (lib "eagle-import") (part "R-US_R0603"))
    )
    (comp (ref "R12")
      (value "470R")
      (footprint "eagle-import:R0603")
      (fields (field (name "PARTNO") "RC0603JR-07470RL"))
      (libsource (lib "eagle-import") (part "R-US_R0603"))
    )
    (comp (ref "R13")
      (value "220k")
      (footprint "eagle-import:R0603")
      (fields (field (name "PARTNO") "RC0603JR-07220KL"))
      (libsource (lib "eagle-import") (part "R-US_R0603"))
    )
    (comp (ref "R14")
      (value "220k")
      (footprint "eagle-import:R0603")
      (fields (field (name "PARTNO") "RC0603JR-07220KL"))
      (libsource (lib "eagle-import") (part "R-US_R0603"))
    )
    (comp (ref "S101")
      (value "SPST-NO")
      (footprint "eagle-import:TACTILE_SWITCH_SMD_6MM_SQ")
      (fields (field (name "PARTNO") "TL3301PF160QG"))
      (libsource (lib "eagle-import") (part "TAC_SWITCH"))
    )
    (comp (ref "U1")
      (value "TPS61200")
      (footprint "eagle-import:QFN-10_PAD")
      (fields (field (name "PARTNO") "TPS61200DRCT"))
      (libsource (lib "eagle-import") (part "TPS61200"))
    )
    (comp (ref "C10")
      (value "0.1uF")
      (footprint "eagle-import:C0603")
      (fields (field (name "PARTNO") "CC0603KRX7R7BB104"))
      (libsource (lib "eagle-import") (part "C-EUC0603"))
    )
    (comp (ref "C12")
      (value "0.1uF")
      (footprint "eagle-import:C0603")
      (fields (field (name "PARTNO") "CC0603KRX7R7BB104"))
      (libsource (lib "eagle-import") (part "resistor_C-EUC0603"))
    )
    (comp (ref "C13")
      (value "10nF")
      (footprint "eagle-import:C0603")
      (fields (field (name "PARTNO") "CC0603KRX7R9BB103"))
      (libsource (lib "eagle-import") (part "resistor_C-EUC0603"))
    )
    (comp (ref "C14")
      (value "22pF")
      (footprint "eagle-import:C0603")
      (fields (field (name "PARTNO") "GRM0335C1E220JD01D"))
      (libsource (lib "eagle-import") (part "resistor_C-EUC0603"))
    )
    (comp (ref "C15")
      (value "10uF")
      (footprint "eagle-import:C0603")
      (fields (field (name "PARTNO") "C1608X5R1A106M"))
      (libsource (lib "eagle-import") (part "resistor_C-EUC0603"))
    )
    (comp (ref "C17")
      (value "1.0uF")
      (footprint "eagle-import:C0603")
      (fields (field (name "PARTNO") "GRM188R61A105KA61D"))
      (libsource (lib "eagle-import") (part "resistor_C-EUC0603"))
    )
    (comp (ref "C20")
      (value "0.1uF")
      (footprint "eagle-import:C0603")
      (fields (field (name "PARTNO") "CC0603KRX7R7BB104"))
      (libsource (lib "eagle-import") (part "resistor_C-EUC0603"))
    )
    (comp (ref "C21")
      (value "47nF")
      (footprint "eagle-import:C0603")
      (fields (field (name "PARTNO") "CC0603KRX7R8BB473"))
      (libsource (lib "eagle-import") (part "resistor_C-EUC0603"))
    )
    (comp (ref "C22")
      (value "22pF")
      (footprint "eagle-import:C0603")
      (fields (field (name "PARTNO") "GRM0335C1E220JD01D"))
      (libsource (lib "eagle-import") (part "resistor_C-EUC0603"))
    )
    (comp (ref "C23")
      (value "10nF")
      (footprint "eagle-import:C0603")
      (fields (field (name "PARTNO") "CC0603KRX7R9BB103"))
      (libsource (lib "eagle-import") (part "resistor_C-EUC0603"))
    )
    (comp (ref "C24")
      (value "0.1uF")
      (footprint "eagle-import:C0603")
      (fields (field (name "PARTNO") "CC0603KRX7R7BB104"))
      (libsource (lib "eagle-import") (part "C-EUC0603"))
    )
    (comp (ref "C25")
      (value "0.1uF")
      (footprint "eagle-import:C0603")
      (fields (field (name "PARTNO") "CC0603KRX7R7BB104"))
      (libsource (lib "eagle-import") (part "resistor_C-EUC0603"))
    )
    (comp (ref "C28")
      (value "0.1uF")
      (footprint "eagle-import:C0603")
      (fields (field (name "PARTNO") "CC0603KRX7R7BB104"))
      (libsource (lib "eagle-import") (part "resistor_C-EUC0603"))
    )
    (comp (ref "C29")
      (value "10uF")
      (footprint "eagle-import:C0603")
      (fields (field (name "PARTNO") "C1608X5R1A106M"))
      (libsource (lib "eagle-import") (part "resistor_C-EUC0603"))
    )
    (comp (ref "C33")
      (value "0.1uF")
      (footprint "eagle-import:C0603")
      (fields (field (name "PARTNO") "CC0603KRX7R7BB104"))
      (libsource (lib "eagle-import") (part "resistor_C-EUC0603"))
    )
    (comp (ref "C34")
      (value "1.0uF")
      (footprint "eagle-import:C0805")
      (fields (field (name "ESR") "LOW ESR") (field (name "PARTNO") "ECP-U1C104MA5"))
      (libsource (lib "eagle-import") (part "C-USC0805"))
    )
    (comp (ref "C39")
      (value "10uF")
      (footprint "eagle-import:C0603")
      (fields (field (name "PARTNO") "C1608X5R1A106M"))
      (libsource (lib "eagle-import") (part "resistor_C-EUC0603"))
    )
    (comp (ref "C40")
      (value "68uF")
      (footprint "eagle-import:CT7343")
      (fields (field (name "ESR") "LOW ESR") (field (name "PARTNO") "T491C686K006AT"))
      (libsource (lib "eagle-import") (part "CPOL-USCT7343"))
    )
    (comp (ref "C41")
      (value "68uF")
      (footprint "eagle-import:CT7343")
      (fields (field (name "ESR") "LOW ESR") (field (name "PARTNO") "T491C686K006AT"))
      (libsource (lib "eagle-import") (part "CPOL-USCT7343"))
    )
    (comp (ref "C45")
      (value "0.1uF")
      (footprint "eagle-import:C0603")
      (fields (field (name "PARTNO") "CC0603KRX7R7BB104"))
      (libsource (lib "eagle-import") (part "resistor_C-EUC0603"))
    )
    (comp (ref "C46")
      (value "0.1uF")
      (footprint "eagle-import:C0603")
      (fields (field (name "PARTNO") "CC0603KRX7R7BB104"))
      (libsource (lib "eagle-import") (part "resistor_C-EUC0603"))
    )
    (comp (ref "C48")
      (value "0.1uF")
      (footprint "eagle-import:C0603")
      (fields (field (name "PARTNO") "CC0603KRX7R7BB104"))
      (libsource (lib "eagle-import") (part "resistor_C-EUC0603"))
    )
    (comp (ref "C49")
      (value "1.0uF")
      (footprint "eagle-import:C0603")
      (fields (field (name "PARTNO") "GRM188R61A105KA61D"))
      (libsource (lib "eagle-import") (part "resistor_C-EUC0603"))
    )
    (comp (ref "C50")
      (value "1.0uF")
      (footprint "eagle-import:C0603")
      (fields (field (name "PARTNO") "GRM188R61A105KA61D"))
      (libsource (lib "eagle-import") (part "resistor_C-EUC0603"))
    )
    (comp (ref "CN2")
      (value "USD-SOCKETNEW")
      (footprint "eagle-import:MICRO-SD-SOCKET-PP")
      (fields (field (name "PARTNO") "101-00581-59"))
      (libsource (lib "eagle-import") (part "USD-SOCKETNEW"))
    )
    (comp (ref "CN9")
      (value "Internal Speaker")
      (footprint "eagle-import:1X03")
      (fields (field (name "PARTNO") "640454-3"))
      (libsource (lib "eagle-import") (part "M03PTH"))
    )
    (comp (ref "CN11")
      (value "AUDIO IN")
      (footprint "eagle-import:STX3100")
      (fields (field (name "PARTNO") "SJ1-3555NG-BE"))
      (libsource (lib "eagle-import") (part "STEREOJACK"))
    )
    (comp (ref "CN12")
      (value "AUDIO OUT")
      (footprint "eagle-import:STX3100")
      (fields (field (name "PARTNO") "SJ1-3555NG-GR"))
      (libsource (lib "eagle-import") (part "STEREOJACK"))
    )
    (comp (ref "LD1")
      (value "GREEN")
      (footprint "eagle-import:CHIP-LED0805")
      (fields (field (name "PARTNO") "LG R971-KN-1-0-20-R18"))
      (libsource (lib "eagle-import") (part "LEDCHIP-LED0805"))
    )
    (comp (ref "LD2")
      (value "GREEN")
      (footprint "eagle-import:CHIP-LED0805")
      (fields (field (name "PARTNO") "LG R971-KN-1-0-20-R18"))
      (libsource (lib "eagle-import") (part "LEDCHIP-LED0805"))
    )
    (comp (ref "R1")
      (value "10K")
      (footprint "eagle-import:R0603")
      (fields (field (name "PARTNO") "RC0603JR-0710KL"))
      (libsource (lib "eagle-import") (part "R-US_R0603"))
    )
    (comp (ref "R5")
      (value "470R")
      (footprint "eagle-import:R0603")
      (fields (field (name "PARTNO") "RC0603JR-07470RL"))
      (libsource (lib "eagle-import") (part "R-US_R0603"))
    )
    (comp (ref "R8")
      (value "470R")
      (footprint "eagle-import:R0603")
      (fields (field (name "PARTNO") "RC0603JR-07470RL"))
      (libsource (lib "eagle-import") (part "R-US_R0603"))
    )
    (comp (ref "R15")
      (value "100K")
      (footprint "eagle-import:R0603")
      (fields (field (name "PARTNO") "RC0603JR-07100KL"))
      (libsource (lib "eagle-import") (part "R-US_R0603"))
    )
    (comp (ref "R19")
      (value "100K")
      (footprint "eagle-import:R0603")
      (fields (field (name "PARTNO") "RC0603JR-07100KL"))
      (libsource (lib "eagle-import") (part "R-US_R0603"))
    )
    (comp (ref "R20")
      (value "100K")
      (footprint "eagle-import:R0603")
      (fields (field (name "PARTNO") "RC0603JR-07100KL"))
      (libsource (lib "eagle-import") (part "R-US_R0603"))
    )
    (comp (ref "R21")
      (value "20R")
      (footprint "eagle-import:R0603")
      (fields (field (name "PARTNO") "RC0603JR-0720RL"))
      (libsource (lib "eagle-import") (part "R-US_R0603"))
    )
    (comp (ref "R24")
      (value "1M")
      (footprint "eagle-import:R0603")
      (fields (field (name "PARTNO") "RC0603JR-071ML"))
      (libsource (lib "eagle-import") (part "R-US_R0603"))
    )
    (comp (ref "R25")
      (value "10R")
      (footprint "eagle-import:R0603")
      (fields (field (name "PARTNO") "RC0603JR-0710RL"))
      (libsource (lib "eagle-import") (part "R-US_R0603"))
    )
    (comp (ref "R26")
      (value "20R")
      (footprint "eagle-import:R0603")
      (fields (field (name "PARTNO") "RC0603JR-0720RL"))
      (libsource (lib "eagle-import") (part "R-US_R0603"))
    )
    (comp (ref "R28")
      (value "100K")
      (footprint "eagle-import:R0603")
      (fields (field (name "PARTNO") "RC0603JR-07100KL"))
      (libsource (lib "eagle-import") (part "R-US_R0603"))
    )
    (comp (ref "R29")
      (value "100K")
      (footprint "eagle-import:R0603")
      (fields (field (name "PARTNO") "RC0603JR-07100KL"))
      (libsource (lib "eagle-import") (part "R-US_R0603"))
    )
    (comp (ref "R30")
      (value "100K")
      (footprint "eagle-import:R0603")
      (fields (field (name "PARTNO") "RC0603JR-07100KL"))
      (libsource (lib "eagle-import") (part "R-US_R0603"))
    )
    (comp (ref "R31")
      (value "100K")
      (footprint "eagle-import:R0603")
      (fields (field (name "PARTNO") "RC0603JR-07100KL"))
      (libsource (lib "eagle-import") (part "R-US_R0603"))
    )
    (comp (ref "R32")
      (value "100K")
      (footprint "eagle-import:R0603")
      (fields (field (name "PARTNO") "RC0603JR-07100KL"))
      (libsource (lib "eagle-import") (part "R-US_R0603"))
    )
    (comp (ref "R33")
      (value "100K")
      (footprint "eagle-import:R0603")
      (fields (field (name "PARTNO") "RC0603JR-07100KL"))
      (libsource (lib "eagle-import") (part "R-US_R0603"))
    )
    (comp (ref "R39")
      (value "100K")
      (footprint "eagle-import:R0603")
      (fields (field (name "PARTNO") "RC0603JR-07100KL"))
      (libsource (lib "eagle-import") (part "R-US_R0603"))
    )
    (comp (ref "R41")
      (value "100K")
      (footprint "eagle-import:R0603")
      (fields (field (name "PARTNO") "RC0603JR-07100KL"))
      (libsource (lib "eagle-import") (part "R-US_R0603"))
    )
    (comp (ref "R46")
      (value "470R")
      (footprint "eagle-import:R0603")
      (fields (field (name "PARTNO") "RC0603JR-07470RL"))
      (libsource (lib "eagle-import") (part "R-US_R0603"))
    )
    (comp (ref "R47")
      (value "100K")
      (footprint "eagle-import:R0603")
      (fields (field (name "PARTNO") "RC0603JR-07100KL"))
      (libsource (lib "eagle-import") (part "R-US_R0603"))
    )
    (comp (ref "R51")
      (value "100K")
      (footprint "eagle-import:R0603")
      (fields (field (name "PARTNO") "RC0603JR-07100KL"))
      (libsource (lib "eagle-import") (part "R-US_R0603"))
    )
    (comp (ref "R52")
      (value "100K")
      (footprint "eagle-import:R0603")
      (fields (field (name "PARTNO") "RC0603JR-07100KL"))
      (libsource (lib "eagle-import") (part "R-US_R0603"))
    )
    (comp (ref "R55")
      (value "470R")
      (footprint "eagle-import:R0603")
      (fields (field (name "PARTNO") "RC0603JR-07470RL"))
      (libsource (lib "eagle-import") (part "R-US_R0603"))
    )
    (comp (ref "R56")
      (value "100K")
      (footprint "eagle-import:R0603")
      (fields (field (name "PARTNO") "RC0603JR-07100KL"))
      (libsource (lib "eagle-import") (part "R-US_R0603"))
    )
    (comp (ref "R57")
      (value "100K")
      (footprint "eagle-import:R0603")
      (fields (field (name "PARTNO") "RC0603JR-07100KL"))
      (libsource (lib "eagle-import") (part "R-US_R0603"))
    )
    (comp (ref "R58")
      (value "100K")
      (footprint "eagle-import:R0603")
      (fields (field (name "PARTNO") "RC0603JR-07100KL"))
      (libsource (lib "eagle-import") (part "R-US_R0603"))
    )
    (comp (ref "R59")
      (value "0R0")
      (footprint "eagle-import:R0603")
      (fields (field (name "DNP") "T") (field (name "PARTNO") "RC0603JR-070RL"))
      (libsource (lib "eagle-import") (part "R-US_R0603"))
    )
    (comp (ref "R62")
      (value "0R0")
      (footprint "eagle-import:R0603")
      (fields (field (name "DNP") "T") (field (name "PARTNO") "RC0603JR-070RL"))
      (libsource (lib "eagle-import") (part "R-US_R0603"))
    )
    (comp (ref "TP1")
      (value "TEST-POINT3X5")
      (footprint "eagle-import:PAD.03X.05")
      (libsource (lib "eagle-import") (part "TEST-POINT3X5"))
    )
    (comp (ref "TP12")
      (value "NSTUFF")
      (footprint "eagle-import:1X01")
      (libsource (lib "eagle-import") (part "PINHD-1X1"))
    )
    (comp (ref "U2")
      (value "BLUETOOTH-RN41")
      (footprint "eagle-import:RN41")
      (fields (field (name "PARTNO") "RN-42"))
      (libsource (lib "eagle-import") (part "BLUETOOTH-RN41{dblquote}"))
    )
    (comp (ref "U4")
      (value "VS1053")
      (footprint "eagle-import:LQFP-48")
      (fields (field (name "PARTNO") "VS1053B-L"))
      (libsource (lib "eagle-import") (part "VS1033"))
    )
    (comp (ref "U5")
      (value "1.8V")
      (footprint "eagle-import:SC70")
      (fields (field (name "PARTNO") "MIC5365-1.8YC5"))
      (libsource (lib "eagle-import") (part "V_REG_LDOSMD2"))
    )
    (comp (ref "U11")
      (value "TPA6100")
      (footprint "eagle-import:SO-08")
      (fields (field (name "PARTNO") "TPA6100A2DR"))
      (libsource (lib "eagle-import") (part "TPA6100"))
    )
    (comp (ref "X3")
      (value "12.288MHz")
      (footprint "eagle-import:CRYSTAL-SMD-5X3")
      (fields (field (name "PARTNO") "ATS122B"))
      (libsource (lib "eagle-import") (part "CRYSTAL5X3"))
    )
    (comp (ref "X4")
      (value "16MHz")
      (footprint "eagle-import:QS_COMBO")
      (fields (field (name "PARTNO") "ATS16B"))
      (libsource (lib "eagle-import") (part "XTAL/S"))
    )
    (comp (ref "Z1")
      (value "PGB1010603")
      (footprint "eagle-import:CT_CN0603")
      (fields (field (name "PARTNO") "PGB1010603MR"))
      (libsource (lib "eagle-import") (part "VARISTORCN0603"))
    )
    (comp (ref "Z2")
      (value "PGB1010603")
      (footprint "eagle-import:CT_CN0603")
      (fields (field (name "PARTNO") "PGB1010603MR"))
      (libsource (lib "eagle-import") (part "VARISTORCN0603"))
    )
    (comp (ref "Z3")
      (value "PGB1010603")
      (footprint "eagle-import:CT_CN0603")
      (fields (field (name "PARTNO") "PGB1010603MR"))
      (libsource (lib "eagle-import") (part "VARISTORCN0603"))
    )
    (comp (ref "Z4")
      (value "PGB1010603")
      (footprint "eagle-import:CT_CN0603")
      (fields (field (name "PARTNO") "PGB1010603MR"))
      (libsource (lib "eagle-import") (part "VARISTORCN0603"))
    )
    (comp (ref "C26")
      (value "0.1uF")
      (footprint "eagle-import:C0603")
      (fields (field (name "PARTNO") "CC0603KRX7R7BB104"))
      (libsource (lib "eagle-import") (part "C-EUC0603"))
    )
    (comp (ref "C30")
      (value "33pF")
      (footprint "eagle-import:C0603")
      (fields (field (name "PARTNO") "GRM0335C1E330JD01D"))
      (libsource (lib "eagle-import") (part "resistor_C-EUC0603"))
    )
    (comp (ref "C31")
      (value "0.1uF")
      (footprint "eagle-import:C0603")
      (fields (field (name "PARTNO") "CC0603KRX7R7BB104"))
      (libsource (lib "eagle-import") (part "resistor_C-EUC0603"))
    )
    (comp (ref "C32")
      (value "0.1uF")
      (footprint "eagle-import:C0603")
      (fields (field (name "PARTNO") "CC0603KRX7R7BB104"))
      (libsource (lib "eagle-import") (part "resistor_C-EUC0603"))
    )
    (comp (ref "C35")
      (value "1.0nF")
      (footprint "eagle-import:C0603")
      (fields (field (name "PARTNO") "CC0603KRX7R9BB102"))
      (libsource (lib "eagle-import") (part "resistor_C-EUC0603"))
    )
    (comp (ref "C36")
      (value "1.0nF")
      (footprint "eagle-import:C0603")
      (fields (field (name "PARTNO") "CC0603KRX7R9BB102"))
      (libsource (lib "eagle-import") (part "resistor_C-EUC0603"))
    )
    (comp (ref "C37")
      (value "33pF")
      (footprint "eagle-import:C0603")
      (fields (field (name "PARTNO") "GRM0335C1E330JD01D"))
      (libsource (lib "eagle-import") (part "resistor_C-EUC0603"))
    )
    (comp (ref "C38")
      (value "1.0nF")
      (footprint "eagle-import:C0603")
      (fields (field (name "PARTNO") "CC0603KRX7R9BB102"))
      (libsource (lib "eagle-import") (part "resistor_C-EUC0603"))
    )
    (comp (ref "C42")
      (value "0.1uF")
      (footprint "eagle-import:C0603")
      (fields (field (name "PARTNO") "CC0603KRX7R7BB104"))
      (libsource (lib "eagle-import") (part "resistor_C-EUC0603"))
    )
    (comp (ref "C43")
      (value "33pF")
      (footprint "eagle-import:C0603")
      (fields (field (name "PARTNO") "GRM0335C1E330JD01D"))
      (libsource (lib "eagle-import") (part "resistor_C-EUC0603"))
    )
    (comp (ref "C44")
      (value "0.1uF")
      (footprint "eagle-import:C0603")
      (fields (field (name "PARTNO") "CC0603KRX7R7BB104"))
      (libsource (lib "eagle-import") (part "resistor_C-EUC0603"))
    )
    (comp (ref "C47")
      (value "1.0nF")
      (footprint "eagle-import:C0603")
      (fields (field (name "PARTNO") "CC0603KRX7R9BB102"))
      (libsource (lib "eagle-import") (part "resistor_C-EUC0603"))
    )
    (comp (ref "C51")
      (value "0.1uF")
      (footprint "eagle-import:C0603")
      (fields (field (name "PARTNO") "CC0603KRX7R7BB104"))
      (libsource (lib "eagle-import") (part "resistor_C-EUC0603"))
    )
    (comp (ref "C52")
      (value "33pF")
      (footprint "eagle-import:C0603")
      (fields (field (name "PARTNO") "GRM0335C1E330JD01D"))
      (libsource (lib "eagle-import") (part "resistor_C-EUC0603"))
    )
    (comp (ref "C53")
      (value "10uF")
      (footprint "eagle-import:C0603")
      (fields (field (name "PARTNO") "C1608X5R1A106M"))
      (libsource (lib "eagle-import") (part "resistor_C-EUC0603"))
    )
    (comp (ref "CN5")
      (value "CONN HEADER PH TOP 2POS 2MM")
      (footprint "eagle-import:1X02")
      (fields (field (name "PARTNO") "B2B-PH-K-S(LF)(SN)"))
      (libsource (lib "eagle-import") (part "M02PTH"))
    )
    (comp (ref "CN6")
      (value "TOUCHPROOF")
      (footprint "eagle-import:TOUCHPROOF1.1MM")
      (fields (field (name "PARTNO") "36619"))
      (libsource (lib "eagle-import") (part "TOUCHPROOF"))
    )
    (comp (ref "CN7")
      (value "TOUCHPROOF")
      (footprint "eagle-import:TOUCHPROOF1.1MM")
      (fields (field (name "PARTNO") "36619"))
      (libsource (lib "eagle-import") (part "TOUCHPROOF"))
    )
    (comp (ref "CN8")
      (value "CONN HEADER PH TOP 2POS 2MM")
      (footprint "eagle-import:1X02")
      (fields (field (name "PARTNO") "B2B-PH-K-S(LF)(SN)"))
      (libsource (lib "eagle-import") (part "M02PTH"))
    )
    (comp (ref "CN10")
      (value "2.5mm(1/4\") Mono")
      (footprint "eagle-import:STEREOJACK2.5MM_SMD")
      (fields (field (name "PARTNO") "MDSMT2ARATRX"))
      (libsource (lib "eagle-import") (part "AUDIOJACK2.5MM_MONO_SWITCH"))
    )
    (comp (ref "R34")
      (value "1.0K")
      (footprint "eagle-import:R0603")
      (fields (field (name "PARTNO") "RC0603JR-071KL"))
      (libsource (lib "eagle-import") (part "R-US_R0603"))
    )
    (comp (ref "R35")
      (value "1.0M")
      (footprint "eagle-import:R0603")
      (fields (field (name "PARTNO") "RC0603JR-071ML"))
      (libsource (lib "eagle-import") (part "R-US_R0603"))
    )
    (comp (ref "R36")
      (value "100K")
      (footprint "eagle-import:R0603")
      (fields (field (name "PARTNO") "RC0603JR-07100KL"))
      (libsource (lib "eagle-import") (part "R-US_R0603"))
    )
    (comp (ref "R37")
      (value "1.0M")
      (footprint "eagle-import:R0603")
      (fields (field (name "PARTNO") "RC0603JR-071ML"))
      (libsource (lib "eagle-import") (part "R-US_R0603"))
    )
    (comp (ref "R38")
      (value "49.9K")
      (footprint "eagle-import:R0603")
      (fields (field (name "PARTNO") "ERJ-3EKF4992V"))
      (libsource (lib "eagle-import") (part "R-US_R0603"))
    )
    (comp (ref "R40")
      (value "0R0")
      (footprint "eagle-import:R0603")
      (fields (field (name "PARTNO") "RC0603JR-070RL"))
      (libsource (lib "eagle-import") (part "R-US_R0603"))
    )
    (comp (ref "R42")
      (value "100K")
      (footprint "eagle-import:R0603")
      (fields (field (name "PARTNO") "RC0603JR-07100KL"))
      (libsource (lib "eagle-import") (part "R-US_R0603"))
    )
    (comp (ref "R43")
      (value "1.0M")
      (footprint "eagle-import:R0603")
      (fields (field (name "PARTNO") "RC0603JR-071ML"))
      (libsource (lib "eagle-import") (part "R-US_R0603"))
    )
    (comp (ref "R44")
      (value "100K")
      (footprint "eagle-import:R0603")
      (fields (field (name "PARTNO") "RC0603JR-07100KL"))
      (libsource (lib "eagle-import") (part "R-US_R0603"))
    )
    (comp (ref "R45")
      (value "10M")
      (footprint "eagle-import:R0603")
      (fields (field (name "PARTNO") "RC0603JR-0710ML"))
      (libsource (lib "eagle-import") (part "R-US_R0603"))
    )
    (comp (ref "R48")
      (value "1.0M")
      (footprint "eagle-import:R0603")
      (fields (field (name "PARTNO") "RC0603JR-071ML"))
      (libsource (lib "eagle-import") (part "R-US_R0603"))
    )
    (comp (ref "R49")
      (value "1.0K")
      (footprint "eagle-import:R0603")
      (fields (field (name "PARTNO") "RC0603JR-071KL"))
      (libsource (lib "eagle-import") (part "R-US_R0603"))
    )
    (comp (ref "R50")
      (value "100K")
      (footprint "eagle-import:R0603")
      (fields (field (name "PARTNO") "RC0603JR-07100KL"))
      (libsource (lib "eagle-import") (part "R-US_R0603"))
    )
    (comp (ref "R53")
      (value "0R0")
      (footprint "eagle-import:R0603")
      (fields (field (name "PARTNO") "RC0603JR-070RL"))
      (libsource (lib "eagle-import") (part "R-US_R0603"))
    )
    (comp (ref "R54")
      (value "100K")
      (footprint "eagle-import:R0603")
      (fields (field (name "PARTNO") "RC0603JR-07100KL"))
      (libsource (lib "eagle-import") (part "R-US_R0603"))
    )
    (comp (ref "R60")
      (value "10K")
      (footprint "eagle-import:R0603")
      (fields (field (name "PARTNO") "RC0603JR-0710KL"))
      (libsource (lib "eagle-import") (part "R-US_R0603"))
    )
    (comp (ref "R61")
      (value "49.9K")
      (footprint "eagle-import:R0603")
      (fields (field (name "PARTNO") "ERJ-3EKF4992V"))
      (libsource (lib "eagle-import") (part "R-US_R0603"))
    )
    (comp (ref "R63")
      (value "100K")
      (footprint "eagle-import:R0603")
      (fields (field (name "PARTNO") "RC0603JR-07100KL"))
      (libsource (lib "eagle-import") (part "R-US_R0603"))
    )
    (comp (ref "U6")
      (value "MCP6S21-I/SN")
      (footprint "eagle-import:SO-08")
      (libsource (lib "eagle-import") (part "MCP6S21"))
    )
    (comp (ref "U7")
      (value "MCP4013")
      (footprint "eagle-import:SOT-23-6")
      (fields (field (name "PARTNO") "MCP4013T-103E/CH"))
      (libsource (lib "eagle-import") (part "MCP4013"))
    )
    (comp (ref "U8")
      (value "MCP4013")
      (footprint "eagle-import:SOT-23-6")
      (fields (field (name "PARTNO") "MCP4013T-103E/CH"))
      (libsource (lib "eagle-import") (part "MCP4013"))
    )
    (comp (ref "U9")
      (value "INA826")
      (footprint "eagle-import:MSOP-8")
      (fields (field (name "PARTNO") "INA826AIDGKR"))
      (libsource (lib "eagle-import") (part "INA826"))
    )
    (comp (ref "U10")
      (value "MCP6S21-I/SN")
      (footprint "eagle-import:SO-08")
      (libsource (lib "eagle-import") (part "MCP6S21"))
    )
    (comp (ref "U12")
      (value "INA826")
      (footprint "eagle-import:MSOP-8")
      (fields (field (name "PARTNO") "INA826AIDGKR"))
      (libsource (lib "eagle-import") (part "INA826"))
    )
  )
  (nets
    (net (code "1") (name "1.8V") (class "Default")
      (node (ref "C10") (pin "1") (pinfunction "1_1") (pintype "passive"))
      (node (ref "C25") (pin "1") (pinfunction "1_1") (pintype "passive"))
      (node (ref "C29") (pin "1") (pinfunction "1_1") (pintype "passive"))
      (node (ref "TP12") (pin "1") (pinfunction "1_1") (pintype "passive"))
      (node (ref "U4") (pin "24") (pinfunction "CVDD3_24") (pintype "bidirectional"))
      (node (ref "U4") (pin "31") (pinfunction "CVDD4_31") (pintype "bidirectional"))
      (node (ref "U4") (pin "5") (pinfunction "CVDD1_5") (pintype "bidirectional"))
      (node (ref "U4") (pin "7") (pinfunction "CVDD2_7") (pintype "bidirectional"))
      (node (ref "U5") (pin "5") (pinfunction "OUT_5") (pintype "passive"))
    )
    (net (code "2") (name "3.3V") (class "Default")
      (node (ref "C12") (pin "1") (pinfunction "1_1") (pintype "passive"))
      (node (ref "C15") (pin "1") (pinfunction "1_1") (pintype "passive"))
      (node (ref "C18") (pin "2") (pinfunction "2_2") (pintype "passive"))
      (node (ref "C20") (pin "1") (pinfunction "1_1") (pintype "passive"))
      (node (ref "C24") (pin "1") (pinfunction "1_1") (pintype "passive"))
      (node (ref "C26") (pin "1") (pinfunction "1_1") (pintype "passive"))
      (node (ref "C27") (pin "2") (pinfunction "2_2") (pintype "passive"))
      (node (ref "C28") (pin "1") (pinfunction "1_1") (pintype "passive"))
      (node (ref "C31") (pin "1") (pinfunction "1_1") (pintype "passive"))
      (node (ref "C32") (pin "1") (pinfunction "1_1") (pintype "passive"))
      (node (ref "C39") (pin "1") (pinfunction "1_1") (pintype "passive"))
      (node (ref "C4") (pin "1") (pinfunction "1_1") (pintype "passive"))
      (node (ref "C42") (pin "1") (pinfunction "1_1") (pintype "passive"))
      (node (ref "C44") (pin "1") (pinfunction "1_1") (pintype "passive"))
      (node (ref "C51") (pin "1") (pinfunction "1_1") (pintype "passive"))
      (node (ref "C53") (pin "1") (pinfunction "1_1") (pintype "passive"))
      (node (ref "C7") (pin "2") (pinfunction "2_2") (pintype "passive"))
      (node (ref "C8") (pin "2") (pinfunction "2_2") (pintype "passive"))
      (node (ref "C9") (pin "2") (pinfunction "2_2") (pintype "passive"))
      (node (ref "CN2") (pin "4") (pinfunction "VCC_4") (pintype "bidirectional"))
      (node (ref "CN3") (pin "4") (pinfunction "4_4") (pintype "passive"))
      (node (ref "CN4") (pin "2") (pinfunction "2_2") (pintype "passive"))
      (node (ref "LD100") (pin "A") (pinfunction "A_A") (pintype "passive"))
      (node (ref "LD101") (pin "A") (pinfunction "A_A") (pintype "passive"))
      (node (ref "LD103") (pin "A") (pinfunction "A_A") (pintype "passive"))
      (node (ref "LD104") (pin "A") (pinfunction "A_A") (pintype "passive"))
      (node (ref "LD105") (pin "A") (pinfunction "A_A") (pintype "passive"))
      (node (ref "LD106") (pin "A") (pinfunction "A_A") (pintype "passive"))
      (node (ref "LD107") (pin "A") (pinfunction "A_A") (pintype "passive"))
      (node (ref "LD108") (pin "A") (pinfunction "A_A") (pintype "passive"))
      (node (ref "LD109") (pin "A") (pinfunction "A_A") (pintype "passive"))
      (node (ref "LD110") (pin "A") (pinfunction "A_A") (pintype "passive"))
      (node (ref "LD111") (pin "A") (pinfunction "A_A") (pintype "passive"))
      (node (ref "LD112") (pin "A") (pinfunction "A_A") (pintype "passive"))
      (node (ref "LD113") (pin "A") (pinfunction "A_A") (pintype "passive"))
      (node (ref "LD114") (pin "A") (pinfunction "A_A") (pintype "passive"))
      (node (ref "LD115") (pin "A") (pinfunction "A_A") (pintype "passive"))
      (node (ref "LD116") (pin "A") (pinfunction "A_A") (pintype "passive"))
      (node (ref "LD117") (pin "A") (pinfunction "A_A") (pintype "passive"))
      (node (ref "LD118") (pin "A") (pinfunction "A_A") (pintype "passive"))
      (node (ref "LD119") (pin "A") (pinfunction "A_A") (pintype "passive"))
      (node (ref "LD120") (pin "A") (pinfunction "A_A") (pintype "passive"))
      (node (ref "LD121") (pin "A") (pinfunction "A_A") (pintype "passive"))
      (node (ref "LD122") (pin "A") (pinfunction "A_A") (pintype "passive"))
      (node (ref "R102") (pin "1") (pinfunction "1_1") (pintype "passive"))
      (node (ref "R103") (pin "1") (pinfunction "1_1") (pintype "passive"))
      (node (ref "R104") (pin "1") (pinfunction "1_1") (pintype "passive"))
      (node (ref "R107") (pin "1") (pinfunction "1_1") (pintype "passive"))
      (node (ref "R11") (pin "2") (pinfunction "2_2") (pintype "passive"))
      (node (ref "R110") (pin "1") (pinfunction "1_1") (pintype "passive"))
      (node (ref "R111") (pin "1") (pinfunction "1_1") (pintype "passive"))
      (node (ref "R114") (pin "1") (pinfunction "1_1") (pintype "passive"))
      (node (ref "R115") (pin "1") (pinfunction "1_1") (pintype "passive"))
      (node (ref "R12") (pin "2") (pinfunction "2_2") (pintype "passive"))
      (node (ref "R14") (pin "2") (pinfunction "2_2") (pintype "passive"))
      (node (ref "R16") (pin "1") (pinfunction "1_1") (pintype "passive"))
      (node (ref "R17") (pin "1") (pinfunction "1_1") (pintype "passive"))
      (node (ref "R18") (pin "1") (pinfunction "1_1") (pintype "passive"))
      (node (ref "R20") (pin "1") (pinfunction "1_1") (pintype "passive"))
      (node (ref "R28") (pin "1") (pinfunction "1_1") (pintype "passive"))
      (node (ref "R30") (pin "2") (pinfunction "2_2") (pintype "passive"))
      (node (ref "R35") (pin "2") (pinfunction "2_2") (pintype "passive"))
      (node (ref "R45") (pin "2") (pinfunction "2_2") (pintype "passive"))
      (node (ref "R48") (pin "2") (pinfunction "2_2") (pintype "passive"))
      (node (ref "R60") (pin "1") (pinfunction "1_1") (pintype "passive"))
      (node (ref "TP14") (pin "1") (pinfunction "1_1") (pintype "passive"))
      (node (ref "TP3") (pin "1") (pinfunction "1_1") (pintype "passive"))
      (node (ref "TP9") (pin "1") (pinfunction "1_1") (pintype "passive"))
      (node (ref "U1") (pin "2") (pinfunction "VOUT_2") (pintype "passive"))
      (node (ref "U10") (pin "8") (pinfunction "VDD_8") (pintype "power_in"))
      (node (ref "U11") (pin "6") (pinfunction "VDD_6") (pintype "power_in"))
      (node (ref "U12") (pin "8") (pinfunction "V+_8") (pintype "power_in"))
      (node (ref "U2") (pin "11") (pinfunction "VDD_11") (pintype "bidirectional"))
      (node (ref "U3") (pin "10") (pinfunction "VCC_10") (pintype "power_in"))
      (node (ref "U3") (pin "100") (pinfunction "AVCC_100") (pintype "power_in"))
      (node (ref "U3") (pin "31") (pinfunction "VCC1_31") (pintype "power_in"))
      (node (ref "U3") (pin "61") (pinfunction "VCC2_61") (pintype "power_in"))
      (node (ref "U3") (pin "80") (pinfunction "VCC3_80") (pintype "power_in"))
      (node (ref "U4") (pin "14") (pinfunction "IOVDD2_14") (pintype "bidirectional"))
      (node (ref "U4") (pin "19") (pinfunction "IOVDD3_19") (pintype "bidirectional"))
      (node (ref "U4") (pin "32") (pinfunction "TEST_32") (pintype "bidirectional"))
      (node (ref "U4") (pin "38") (pinfunction "AVDD1_38") (pintype "bidirectional"))
      (node (ref "U4") (pin "43") (pinfunction "AVDD2_43") (pintype "bidirectional"))
      (node (ref "U4") (pin "45") (pinfunction "AVDD3_45") (pintype "bidirectional"))
      (node (ref "U4") (pin "6") (pinfunction "IOVDD1_6") (pintype "bidirectional"))
      (node (ref "U5") (pin "1") (pinfunction "IN_1") (pintype "input"))
      (node (ref "U5") (pin "3") (pinfunction "EN_3") (pintype "input"))
      (node (ref "U6") (pin "8") (pinfunction "VDD_8") (pintype "power_in"))
      (node (ref "U7") (pin "1") (pinfunction "VDD_1") (pintype "power_in"))
      (node (ref "U7") (pin "6") (pinfunction "A_6") (pintype "passive"))
      (node (ref "U8") (pin "1") (pinfunction "VDD_1") (pintype "power_in"))
      (node (ref "U8") (pin "6") (pinfunction "A_6") (pintype "passive"))
      (node (ref "U9") (pin "8") (pinfunction "V+_8") (pintype "power_in"))
    )
    (net (code "3") (name "AMP_SHTDWN") (class "Default")
      (node (ref "U11") (pin "3") (pinfunction "SHUTDOWN_3") (pintype "input"))
      (node (ref "U3") (pin "4") (pinfunction "(XCK0/AIN0)PE2_4") (pintype "bidirectional"))
    )
    (net (code "4") (name "ANA_BATTERY") (class "Default")
      (node (ref "R3") (pin "1") (pinfunction "1_1") (pintype "passive"))
      (node (ref "R4") (pin "2") (pinfunction "2_2") (pintype "passive"))
      (node (ref "U3") (pin "90") (pinfunction "(ADC7/TDI)PF7_90") (pintype "bidirectional"))
    )
    (net (code "5") (name "ANA_GSR") (class "Default")
      (node (ref "R49") (pin "1") (pinfunction "1_1") (pintype "passive"))
      (node (ref "U3") (pin "97") (pinfunction "(ADC0)PF0_97") (pintype "bidirectional"))
    )
    (net (code "6") (name "ANA_TMP") (class "Default")
      (node (ref "R34") (pin "1") (pinfunction "1_1") (pintype "passive"))
      (node (ref "U3") (pin "96") (pinfunction "(ADC1)PF1_96") (pintype "bidirectional"))
    )
    (net (code "7") (name "ARDUINO_DTR") (class "Default")
      (node (ref "C6") (pin "1") (pinfunction "1_1") (pintype "passive"))
      (node (ref "CN3") (pin "1") (pinfunction "1_1") (pintype "passive"))
    )
    (net (code "8") (name "ARDUINO_TX0") (class "Default")
      (node (ref "CN3") (pin "2") (pinfunction "2_2") (pintype "passive"))
      (node (ref "U3") (pin "3") (pinfunction "(TXD0)PE1_3") (pintype "bidirectional"))
    )
    (net (code "9") (name "ARDUINO_\\RX0") (class "Default")
      (node (ref "CN3") (pin "3") (pinfunction "3_3") (pintype "passive"))
      (node (ref "U3") (pin "2") (pinfunction "(RXD0/PCIN8)PE0_2") (pintype "bidirectional"))
    )
    (net (code "10") (name "AREF") (class "Default")
      (node (ref "C16") (pin "2") (pinfunction "2_2") (pintype "passive"))
      (node (ref "U3") (pin "98") (pinfunction "AREF_98") (pintype "bidirectional"))
    )
    (net (code "11") (name "BT_CTS") (class "Default")
      (node (ref "U2") (pin "16") (pinfunction "UARTCTS_16") (pintype "bidirectional"))
      (node (ref "U3") (pin "73") (pinfunction "(AD5)PA5_73") (pintype "bidirectional"))
    )
    (net (code "12") (name "BT_RST") (class "Default")
      (node (ref "R15") (pin "1") (pinfunction "1_1") (pintype "passive"))
      (node (ref "U2") (pin "5") (pinfunction "RESET_5") (pintype "bidirectional"))
      (node (ref "U3") (pin "77") (pinfunction "(AD1)PA1_77") (pintype "bidirectional"))
    )
    (net (code "13") (name "BT_RX") (class "Default")
      (node (ref "U2") (pin "13") (pinfunction "UARTRX_13") (pintype "bidirectional"))
      (node (ref "U3") (pin "64") (pinfunction "PJ1(TXD3/PCINT10)_64") (pintype "bidirectional"))
    )
    (net (code "14") (name "BT_TX") (class "Default")
      (node (ref "U2") (pin "14") (pinfunction "UARTTX_14") (pintype "bidirectional"))
      (node (ref "U3") (pin "63") (pinfunction "PJ0(RXD3/PCINT9)_63") (pintype "bidirectional"))
    )
    (net (code "15") (name "BT_\\RTS") (class "Default")
      (node (ref "U2") (pin "15") (pinfunction "UARTRTS_15") (pintype "bidirectional"))
      (node (ref "U3") (pin "74") (pinfunction "(AD4)PA4_74") (pintype "bidirectional"))
    )
    (net (code "16") (name "B_AUDIO") (class "Default")
      (node (ref "R107") (pin "2") (pinfunction "2_2") (pintype "passive"))
      (node (ref "S104") (pin "4") (pinfunction "4_4") (pintype "passive"))
      (node (ref "U3") (pin "49") (pinfunction "(T1)PD6_49") (pintype "bidirectional"))
    )
    (net (code "17") (name "B_CH1") (class "Default")
      (node (ref "R115") (pin "2") (pinfunction "2_2") (pintype "passive"))
      (node (ref "S107") (pin "4") (pinfunction "4_4") (pintype "passive"))
      (node (ref "U3") (pin "88") (pinfunction "PK1(ADC9/PCINT17)_88") (pintype "bidirectional"))
    )
    (net (code "18") (name "B_CH2") (class "Default")
      (node (ref "R104") (pin "2") (pinfunction "2_2") (pintype "passive"))
      (node (ref "S103") (pin "4") (pinfunction "4_4") (pintype "passive"))
      (node (ref "U3") (pin "79") (pinfunction "PJ7_79") (pintype "bidirectional"))
    )
    (net (code "19") (name "B_CNTR") (class "Default")
      (node (ref "R103") (pin "2") (pinfunction "2_2") (pintype "passive"))
      (node (ref "S102") (pin "4") (pinfunction "4_4") (pintype "passive"))
      (node (ref "U3") (pin "72") (pinfunction "(AD6)PA6_72") (pintype "bidirectional"))
    )
    (net (code "20") (name "B_DISP") (class "Default")
      (node (ref "R114") (pin "2") (pinfunction "2_2") (pintype "passive"))
      (node (ref "S108") (pin "4") (pinfunction "4_4") (pintype "passive"))
      (node (ref "U3") (pin "14") (pinfunction "PH2(XCK2)_14") (pintype "bidirectional"))
    )
    (net (code "21") (name "B_DWN") (class "Default")
      (node (ref "R110") (pin "2") (pinfunction "2_2") (pintype "passive"))
      (node (ref "S105") (pin "4") (pinfunction "4_4") (pintype "passive"))
      (node (ref "U3") (pin "82") (pinfunction "PK7(ADC15/PCINT23)_82") (pintype "bidirectional"))
    )
    (net (code "22") (name "B_ONOFF_SNS") (class "Default")
      (node (ref "Q2") (pin "C") (pinfunction "C_C") (pintype "passive"))
      (node (ref "R14") (pin "1") (pinfunction "1_1") (pintype "passive"))
      (node (ref "U3") (pin "53") (pinfunction "(A8)PC0_53") (pintype "bidirectional"))
    )
    (net (code "23") (name "B_THR") (class "Default")
      (node (ref "R102") (pin "2") (pinfunction "2_2") (pintype "passive"))
      (node (ref "S100") (pin "4") (pinfunction "4_4") (pintype "passive"))
      (node (ref "U3") (pin "78") (pinfunction "(AD0)PA0_78") (pintype "bidirectional"))
    )
    (net (code "24") (name "B_UP") (class "Default")
      (node (ref "R111") (pin "2") (pinfunction "2_2") (pintype "passive"))
      (node (ref "S106") (pin "4") (pinfunction "4_4") (pintype "passive"))
      (node (ref "U3") (pin "35") (pinfunction "PL0(ICP4)_35") (pintype "bidirectional"))
    )
    (net (code "25") (name "GBUF") (class "Default")
      (node (ref "R25") (pin "2") (pinfunction "2_2") (pintype "passive"))
      (node (ref "U4") (pin "42") (pinfunction "GBUF_42") (pintype "bidirectional"))
    )
    (net (code "26") (name "GND") (class "Default")
      (node (ref "C10") (pin "2") (pinfunction "2_2") (pintype "passive"))
      (node (ref "C11") (pin "1") (pinfunction "1_1") (pintype "passive"))
      (node (ref "C12") (pin "2") (pinfunction "2_2") (pintype "passive"))
      (node (ref "C13") (pin "2") (pinfunction "2_2") (pintype "passive"))
      (node (ref "C14") (pin "1") (pinfunction "1_1") (pintype "passive"))
      (node (ref "C15") (pin "2") (pinfunction "2_2") (pintype "passive"))
      (node (ref "C16") (pin "1") (pinfunction "1_1") (pintype "passive"))
      (node (ref "C17") (pin "1") (pinfunction "1_1") (pintype "passive"))
      (node (ref "C18") (pin "1") (pinfunction "1_1") (pintype "passive"))
      (node (ref "C19") (pin "1") (pinfunction "1_1") (pintype "passive"))
      (node (ref "C2") (pin "2") (pinfunction "2_2") (pintype "passive"))
      (node (ref "C20") (pin "2") (pinfunction "2_2") (pintype "passive"))
      (node (ref "C21") (pin "2") (pinfunction "2_2") (pintype "passive"))
      (node (ref "C22") (pin "1") (pinfunction "1_1") (pintype "passive"))
      (node (ref "C23") (pin "2") (pinfunction "2_2") (pintype "passive"))
      (node (ref "C24") (pin "2") (pinfunction "2_2") (pintype "passive"))
      (node (ref "C25") (pin "2") (pinfunction "2_2") (pintype "passive"))
      (node (ref "C26") (pin "2") (pinfunction "2_2") (pintype "passive"))
      (node (ref "C27") (pin "1") (pinfunction "1_1") (pintype "passive"))
      (node (ref "C28") (pin "2") (pinfunction "2_2") (pintype "passive"))
      (node (ref "C29") (pin "2") (pinfunction "2_2") (pintype "passive"))
      (node (ref "C3") (pin "2") (pinfunction "2_2") (pintype "passive"))
      (node (ref "C30") (pin "1") (pinfunction "1_1") (pintype "passive"))
      (node (ref "C31") (pin "2") (pinfunction "2_2") (pintype "passive"))
      (node (ref "C32") (pin "2") (pinfunction "2_2") (pintype "passive"))
      (node (ref "C34") (pin "2") (pinfunction "2_2") (pintype "passive"))
      (node (ref "C35") (pin "2") (pinfunction "2_2") (pintype "passive"))
      (node (ref "C37") (pin "1") (pinfunction "1_1") (pintype "passive"))
      (node (ref "C39") (pin "2") (pinfunction "2_2") (pintype "passive"))
      (node (ref "C4") (pin "2") (pinfunction "2_2") (pintype "passive"))
      (node (ref "C42") (pin "2") (pinfunction "2_2") (pintype "passive"))
      (node (ref "C43") (pin "2") (pinfunction "2_2") (pintype "passive"))
      (node (ref "C44") (pin "2") (pinfunction "2_2") (pintype "passive"))
      (node (ref "C47") (pin "2") (pinfunction "2_2") (pintype "passive"))
      (node (ref "C5") (pin "2") (pinfunction "2_2") (pintype "passive"))
      (node (ref "C51") (pin "2") (pinfunction "2_2") (pintype "passive"))
      (node (ref "C52") (pin "2") (pinfunction "2_2") (pintype "passive"))
      (node (ref "C53") (pin "2") (pinfunction "2_2") (pintype "passive"))
      (node (ref "C7") (pin "1") (pinfunction "1_1") (pintype "passive"))
      (node (ref "C8") (pin "1") (pinfunction "1_1") (pintype "passive"))
      (node (ref "C9") (pin "1") (pinfunction "1_1") (pintype "passive"))
      (node (ref "CN1") (pin "2") (pinfunction "2_2") (pintype "passive"))
      (node (ref "CN10") (pin "5") (pinfunction "5_5") (pintype "passive"))
      (node (ref "CN10") (pin "A") (pinfunction "A_A") (pintype "passive"))
      (node (ref "CN11") (pin "1") (pinfunction "1_1") (pintype "passive"))
      (node (ref "CN11") (pin "3") (pinfunction "3_3") (pintype "passive"))
      (node (ref "CN11") (pin "4") (pinfunction "4_4") (pintype "passive"))
      (node (ref "CN12") (pin "1") (pinfunction "1_1") (pintype "passive"))
      (node (ref "CN2") (pin "6") (pinfunction "GND_6") (pintype "bidirectional"))
      (node (ref "CN2") (pin "CD1") (pinfunction "SHIELD_CD1") (pintype "bidirectional"))
      (node (ref "CN2") (pin "CD2") (pinfunction "SHIELD_CD2") (pintype "bidirectional"))
      (node (ref "CN2") (pin "GND1") (pinfunction "SHIELD_GND1") (pintype "bidirectional"))
      (node (ref "CN2") (pin "GND3") (pinfunction "SHIELD_GND3") (pintype "bidirectional"))
      (node (ref "CN3") (pin "5") (pinfunction "5_5") (pintype "passive"))
      (node (ref "CN3") (pin "6") (pinfunction "6_6") (pintype "passive"))
      (node (ref "CN4") (pin "6") (pinfunction "6_6") (pintype "passive"))
      (node (ref "CN5") (pin "2") (pinfunction "2_2") (pintype "passive"))
      (node (ref "CN6") (pin "P$1") (pinfunction "1_P$1") (pintype "passive"))
      (node (ref "CN8") (pin "1") (pinfunction "1_1") (pintype "passive"))
      (node (ref "CN9") (pin "1") (pinfunction "1_1") (pintype "passive"))
      (node (ref "LD102") (pin "C") (pinfunction "C_C") (pintype "passive"))
      (node (ref "LD3") (pin "C") (pinfunction "C_C") (pintype "passive"))
      (node (ref "Q1") (pin "1") (pinfunction "E_1") (pintype "passive"))
      (node (ref "Q2") (pin "E") (pinfunction "E_E") (pintype "passive"))
      (node (ref "R1") (pin "1") (pinfunction "1_1") (pintype "passive"))
      (node (ref "R13") (pin "1") (pinfunction "1_1") (pintype "passive"))
      (node (ref "R15") (pin "2") (pinfunction "2_2") (pintype "passive"))
      (node (ref "R19") (pin "1") (pinfunction "1_1") (pintype "passive"))
      (node (ref "R2") (pin "1") (pinfunction "1_1") (pintype "passive"))
      (node (ref "R29") (pin "1") (pinfunction "1_1") (pintype "passive"))
      (node (ref "R31") (pin "1") (pinfunction "1_1") (pintype "passive"))
      (node (ref "R32") (pin "1") (pinfunction "1_1") (pintype "passive"))
      (node (ref "R33") (pin "1") (pinfunction "1_1") (pintype "passive"))
      (node (ref "R37") (pin "1") (pinfunction "1_1") (pintype "passive"))
      (node (ref "R4") (pin "1") (pinfunction "1_1") (pintype "passive"))
      (node (ref "R40") (pin "1") (pinfunction "1_1") (pintype "passive"))
      (node (ref "R41") (pin "2") (pinfunction "2_2") (pintype "passive"))
      (node (ref "R43") (pin "1") (pinfunction "1_1") (pintype "passive"))
      (node (ref "R5") (pin "2") (pinfunction "2_2") (pintype "passive"))
      (node (ref "R53") (pin "1") (pinfunction "1_1") (pintype "passive"))
      (node (ref "R57") (pin "2") (pinfunction "2_2") (pintype "passive"))
      (node (ref "R7") (pin "1") (pinfunction "1_1") (pintype "passive"))
      (node (ref "R8") (pin "2") (pinfunction "2_2") (pintype "passive"))
      (node (ref "R9") (pin "1") (pinfunction "1_1") (pintype "passive"))
      (node (ref "S100") (pin "2") (pinfunction "2_2") (pintype "passive"))
      (node (ref "S102") (pin "2") (pinfunction "2_2") (pintype "passive"))
      (node (ref "S103") (pin "2") (pinfunction "2_2") (pintype "passive"))
      (node (ref "S104") (pin "2") (pinfunction "2_2") (pintype "passive"))
      (node (ref "S105") (pin "2") (pinfunction "2_2") (pintype "passive"))
      (node (ref "S106") (pin "2") (pinfunction "2_2") (pintype "passive"))
      (node (ref "S107") (pin "2") (pinfunction "2_2") (pintype "passive"))
      (node (ref "S108") (pin "2") (pinfunction "2_2") (pintype "passive"))
      (node (ref "TP13") (pin "1") (pinfunction "1_1") (pintype "passive"))
      (node (ref "TP15") (pin "1") (pinfunction "1_1") (pintype "passive"))
      (node (ref "TP2") (pin "1") (pinfunction "1_1") (pintype "passive"))
      (node (ref "TP4") (pin "1") (pinfunction "1_1") (pintype "passive"))
      (node (ref "U1") (pin "11") (pinfunction "PAD_11") (pintype "power_in"))
      (node (ref "U1") (pin "12") (pinfunction "PAD_12") (pintype "power_in"))
      (node (ref "U1") (pin "13") (pinfunction "PAD_13") (pintype "power_in"))
      (node (ref "U1") (pin "14") (pinfunction "PAD_14") (pintype "power_in"))
      (node (ref "U1") (pin "15") (pinfunction "PAD_15") (pintype "power_in"))
      (node (ref "U1") (pin "4") (pinfunction "PGND_4") (pintype "power_in"))
      (node (ref "U1") (pin "9") (pinfunction "GND_9") (pintype "power_in"))
      (node (ref "U10") (pin "3") (pinfunction "VREF_3") (pintype "passive"))
      (node (ref "U10") (pin "4") (pinfunction "VSS_4") (pintype "power_in"))
      (node (ref "U11") (pin "2") (pinfunction "GND_2") (pintype "power_in"))
      (node (ref "U12") (pin "5") (pinfunction "V-_5") (pintype "power_in"))
      (node (ref "U2") (pin "1") (pinfunction "GND_1") (pintype "bidirectional"))
      (node (ref "U2") (pin "12") (pinfunction "GND1_12") (pintype "bidirectional"))
      (node (ref "U2") (pin "25") (pinfunction "GND2_25") (pintype "bidirectional"))
      (node (ref "U2") (pin "27") (pinfunction "GND3_27") (pintype "bidirectional"))
      (node (ref "U2") (pin "28") (pinfunction "GND4_28") (pintype "bidirectional"))
      (node (ref "U2") (pin "29") (pinfunction "GND5_29") (pintype "bidirectional"))
      (node (ref "U3") (pin "11") (pinfunction "GND_11") (pintype "power_in"))
      (node (ref "U3") (pin "32") (pinfunction "GND1_32") (pintype "power_in"))
      (node (ref "U3") (pin "62") (pinfunction "GND2_62") (pintype "power_in"))
      (node (ref "U3") (pin "81") (pinfunction "GND3_81") (pintype "power_in"))
      (node (ref "U3") (pin "99") (pinfunction "AGND_99") (pintype "power_in"))
      (node (ref "U4") (pin "16") (pinfunction "DGND2_16") (pintype "bidirectional"))
      (node (ref "U4") (pin "20") (pinfunction "DGND3_20") (pintype "bidirectional"))
      (node (ref "U4") (pin "21") (pinfunction "DGND4_21") (pintype "bidirectional"))
      (node (ref "U4") (pin "22") (pinfunction "DGND5_22") (pintype "bidirectional"))
      (node (ref "U4") (pin "35") (pinfunction "DGND6_35") (pintype "bidirectional"))
      (node (ref "U4") (pin "37") (pinfunction "AGND1_37") (pintype "bidirectional"))
      (node (ref "U4") (pin "4") (pinfunction "DGND1_4") (pintype "bidirectional"))
      (node (ref "U4") (pin "40") (pinfunction "AGND2_40") (pintype "bidirectional"))
      (node (ref "U4") (pin "41") (pinfunction "AGND3_41") (pintype "bidirectional"))
      (node (ref "U4") (pin "47") (pinfunction "AGND4_47") (pintype "bidirectional"))
      (node (ref "U5") (pin "2") (pinfunction "GND_2") (pintype "input"))
      (node (ref "U6") (pin "3") (pinfunction "VREF_3") (pintype "passive"))
      (node (ref "U6") (pin "4") (pinfunction "VSS_4") (pintype "power_in"))
      (node (ref "U7") (pin "2") (pinfunction "VSS_2") (pintype "power_in"))
      (node (ref "U8") (pin "2") (pinfunction "VSS_2") (pintype "power_in"))
      (node (ref "U9") (pin "5") (pinfunction "V-_5") (pintype "power_in"))
      (node (ref "X1") (pin "2") (pinfunction "2_2") (pintype "passive"))
      (node (ref "Z1") (pin "2") (pinfunction "2_2") (pintype "passive"))
      (node (ref "Z2") (pin "2") (pinfunction "2_2") (pintype "passive"))
      (node (ref "Z3") (pin "2") (pinfunction "2_2") (pintype "passive"))
      (node (ref "Z4") (pin "2") (pinfunction "2_2") (pintype "passive"))
    )
    (net (code "27") (name "GSR+") (class "Default")
      (node (ref "CN5") (pin "1") (pinfunction "1_1") (pintype "passive"))
      (node (ref "CN7") (pin "P$1") (pinfunction "1_P$1") (pintype "passive"))
      (node (ref "R45") (pin "1") (pinfunction "1_1") (pintype "passive"))
      (node (ref "R50") (pin "1") (pinfunction "1_1") (pintype "passive"))
    )
    (net (code "28") (name "GSROF_CS") (class "Default")
      (node (ref "U3") (pin "19") (pinfunction "(SS/PCINT0)PB0_19") (pintype "bidirectional"))
      (node (ref "U7") (pin "4") (pinfunction "CS_4") (pintype "passive"))
    )
    (net (code "29") (name "GSR_CS") (class "Default")
      (node (ref "U10") (pin "5") (pinfunction "CS_5") (pintype "input"))
      (node (ref "U3") (pin "8") (pinfunction "(T3/INT6)PE6_8") (pintype "bidirectional"))
    )
    (net (code "30") (name "LD17") (class "Default")
      (node (ref "R27") (pin "2") (pinfunction "2_2") (pintype "passive"))
      (node (ref "U3") (pin "26") (pinfunction "(OC0A/OC1C/PCINT7)PB7_26") (pintype "bidirectional"))
    )
    (net (code "31") (name "LD_BAR01") (class "Default")
      (node (ref "R118") (pin "2") (pinfunction "2_2") (pintype "passive"))
      (node (ref "U3") (pin "40") (pinfunction "PL5(OC5C)_40") (pintype "bidirectional"))
    )
    (net (code "32") (name "LD_BAR02") (class "Default")
      (node (ref "R117") (pin "2") (pinfunction "2_2") (pintype "passive"))
      (node (ref "U3") (pin "39") (pinfunction "PL4(OC5B)_39") (pintype "bidirectional"))
    )
    (net (code "33") (name "LD_BAR03") (class "Default")
      (node (ref "R116") (pin "2") (pinfunction "2_2") (pintype "passive"))
      (node (ref "U3") (pin "38") (pinfunction "PL3(OC5A)_38") (pintype "bidirectional"))
    )
    (net (code "34") (name "LD_BAR04") (class "Default")
      (node (ref "R129") (pin "2") (pinfunction "2_2") (pintype "passive"))
      (node (ref "U3") (pin "25") (pinfunction "(OC1B/PCINT6)PB6_25") (pintype "bidirectional"))
    )
    (net (code "35") (name "LD_BAR05") (class "Default")
      (node (ref "R128") (pin "2") (pinfunction "2_2") (pintype "passive"))
      (node (ref "U3") (pin "24") (pinfunction "(OC1A/PCINT5)PB5_24") (pintype "bidirectional"))
    )
    (net (code "36") (name "LD_BAR06") (class "Default")
      (node (ref "R127") (pin "2") (pinfunction "2_2") (pintype "passive"))
      (node (ref "U3") (pin "23") (pinfunction "(OC2A/PCINT4)PB4_23") (pintype "bidirectional"))
    )
    (net (code "37") (name "LD_BAR07") (class "Default")
      (node (ref "R126") (pin "2") (pinfunction "2_2") (pintype "passive"))
      (node (ref "U3") (pin "18") (pinfunction "PH6(OC2B)_18") (pintype "bidirectional"))
    )
    (net (code "38") (name "LD_BAR08") (class "Default")
      (node (ref "R125") (pin "2") (pinfunction "2_2") (pintype "passive"))
      (node (ref "U3") (pin "17") (pinfunction "PH5(OC4C)_17") (pintype "bidirectional"))
    )
    (net (code "39") (name "LD_BAR09") (class "Default")
      (node (ref "R124") (pin "2") (pinfunction "2_2") (pintype "passive"))
      (node (ref "U3") (pin "16") (pinfunction "PH4(OC4B)_16") (pintype "bidirectional"))
    )
    (net (code "40") (name "LD_BAR10") (class "Default")
      (node (ref "R123") (pin "2") (pinfunction "2_2") (pintype "passive"))
      (node (ref "U3") (pin "15") (pinfunction "PH3(OC4A)_15") (pintype "bidirectional"))
    )
    (net (code "41") (name "LD_BAR11") (class "Default")
      (node (ref "R122") (pin "2") (pinfunction "2_2") (pintype "passive"))
      (node (ref "U3") (pin "7") (pinfunction "(OC3C/INT5)PE5_7") (pintype "bidirectional"))
    )
    (net (code "42") (name "LD_BAR12") (class "Default")
      (node (ref "R121") (pin "2") (pinfunction "2_2") (pintype "passive"))
      (node (ref "U3") (pin "6") (pinfunction "(OC3B/INT4)PE4_6") (pintype "bidirectional"))
    )
    (net (code "43") (name "LD_BAR13") (class "Default")
      (node (ref "R120") (pin "2") (pinfunction "2_2") (pintype "passive"))
      (node (ref "U3") (pin "5") (pinfunction "(OC3A/AIN1)PE3_5") (pintype "bidirectional"))
    )
    (net (code "44") (name "LD_BAR14") (class "Default")
      (node (ref "R119") (pin "2") (pinfunction "2_2") (pintype "passive"))
      (node (ref "U3") (pin "1") (pinfunction "(OC0B)PG5_1") (pintype "bidirectional"))
    )
    (net (code "45") (name "LD_DWN") (class "Default")
      (node (ref "R108") (pin "2") (pinfunction "2_2") (pintype "passive"))
      (node (ref "U3") (pin "87") (pinfunction "PK2(ADC10/PCINT18)_87") (pintype "bidirectional"))
    )
    (net (code "46") (name "LD_GSR1") (class "Default")
      (node (ref "R113") (pin "2") (pinfunction "2_2") (pintype "passive"))
      (node (ref "U3") (pin "9") (pinfunction "(CLKO/ICP3/INT7)PE7_9") (pintype "bidirectional"))
    )
    (net (code "47") (name "LD_GSR2") (class "Default")
      (node (ref "R106") (pin "2") (pinfunction "2_2") (pintype "passive"))
      (node (ref "U3") (pin "50") (pinfunction "(T0)PD7_50") (pintype "bidirectional"))
    )
    (net (code "48") (name "LD_THR_ABV") (class "Default")
      (node (ref "R100") (pin "2") (pinfunction "2_2") (pintype "passive"))
      (node (ref "U3") (pin "70") (pinfunction "(ALE)PG2_70") (pintype "bidirectional"))
    )
    (net (code "49") (name "LD_THR_BLW") (class "Default")
      (node (ref "R101") (pin "2") (pinfunction "2_2") (pintype "passive"))
      (node (ref "U3") (pin "76") (pinfunction "(AD2)PA2_76") (pintype "bidirectional"))
    )
    (net (code "50") (name "LD_TMP1") (class "Default")
      (node (ref "R112") (pin "2") (pinfunction "2_2") (pintype "passive"))
      (node (ref "U3") (pin "89") (pinfunction "PK0(ADC8/PCINT16)_89") (pintype "bidirectional"))
    )
    (net (code "51") (name "LD_TMP2") (class "Default")
      (node (ref "R105") (pin "2") (pinfunction "2_2") (pintype "passive"))
      (node (ref "U3") (pin "75") (pinfunction "(AD3)PA3_75") (pintype "bidirectional"))
    )
    (net (code "52") (name "LD_UP") (class "Default")
      (node (ref "R109") (pin "2") (pinfunction "2_2") (pintype "passive"))
      (node (ref "U3") (pin "36") (pinfunction "PL1(ICP5)_36") (pintype "bidirectional"))
    )
    (net (code "53") (name "LEFTIN") (class "Default")
      (node (ref "C46") (pin "1") (pinfunction "1_1") (pintype "passive"))
      (node (ref "C50") (pin "1") (pinfunction "1_1") (pintype "passive"))
      (node (ref "CN11") (pin "5") (pinfunction "5_5") (pintype "passive"))
      (node (ref "Z2") (pin "1") (pinfunction "1_1") (pintype "passive"))
    )
    (net (code "54") (name "LEFTOUT") (class "Default")
      (node (ref "C41") (pin "-") (pinfunction "-_-") (pintype "passive"))
      (node (ref "CN12") (pin "5") (pinfunction "5_5") (pintype "passive"))
      (node (ref "R62") (pin "1") (pinfunction "1_1") (pintype "passive"))
      (node (ref "Z4") (pin "1") (pinfunction "1_1") (pintype "passive"))
    )
    (net (code "55") (name "MIDI_RX") (class "Default")
      (node (ref "R30") (pin "1") (pinfunction "1_1") (pintype "passive"))
      (node (ref "U3") (pin "13") (pinfunction "PH1(TXD2)_13") (pintype "bidirectional"))
      (node (ref "U4") (pin "26") (pinfunction "RX_26") (pintype "bidirectional"))
    )
    (net (code "56") (name "MIDI_TX") (class "Default")
      (node (ref "U3") (pin "12") (pinfunction "PH0(RXD2)_12") (pintype "bidirectional"))
      (node (ref "U4") (pin "27") (pinfunction "TX_27") (pintype "bidirectional"))
    )
    (net (code "57") (name "MISO") (class "Default")
      (node (ref "CN2") (pin "7") (pinfunction "DO_7") (pintype "bidirectional"))
      (node (ref "CN4") (pin "1") (pinfunction "1_1") (pintype "passive"))
      (node (ref "TP7") (pin "1") (pinfunction "1_1") (pintype "passive"))
      (node (ref "U3") (pin "22") (pinfunction "(MISO/PCINT3)PB3_22") (pintype "bidirectional"))
      (node (ref "U4") (pin "30") (pinfunction "S0_30") (pintype "bidirectional"))
    )
    (net (code "58") (name "MOSI") (class "Default")
      (node (ref "CN2") (pin "3") (pinfunction "DI_3") (pintype "bidirectional"))
      (node (ref "CN4") (pin "4") (pinfunction "4_4") (pintype "passive"))
      (node (ref "TP5") (pin "1") (pinfunction "1_1") (pintype "passive"))
      (node (ref "U10") (pin "6") (pinfunction "SI_6") (pintype "input"))
      (node (ref "U3") (pin "21") (pinfunction "(MOSI/PCINT2)PB2_21") (pintype "bidirectional"))
      (node (ref "U4") (pin "29") (pinfunction "SI_29") (pintype "bidirectional"))
      (node (ref "U6") (pin "6") (pinfunction "SI_6") (pintype "input"))
      (node (ref "U7") (pin "3") (pinfunction "U/D_3") (pintype "bidirectional"))
      (node (ref "U8") (pin "3") (pinfunction "U/D_3") (pintype "bidirectional"))
    )
    (net (code "59") (name "MP3GPIO0") (class "Default")
      (node (ref "R31") (pin "2") (pinfunction "2_2") (pintype "passive"))
      (node (ref "U4") (pin "33") (pinfunction "GPIO0/I2S_SCLK_33") (pintype "bidirectional"))
    )
    (net (code "60") (name "MP3GPIO1") (class "Default")
      (node (ref "R28") (pin "2") (pinfunction "2_2") (pintype "passive"))
      (node (ref "R32") (pin "2") (pinfunction "2_2") (pintype "passive"))
      (node (ref "U4") (pin "34") (pinfunction "GPIO1/I2S_SDATA_34") (pintype "bidirectional"))
    )
    (net (code "61") (name "MP3LEFTOUT") (class "Default")
      (node (ref "C48") (pin "1") (pinfunction "1_1") (pintype "passive"))
      (node (ref "R21") (pin "2") (pinfunction "2_2") (pintype "passive"))
      (node (ref "R62") (pin "2") (pinfunction "2_2") (pintype "passive"))
      (node (ref "U4") (pin "46") (pinfunction "LEFT_46") (pintype "bidirectional"))
    )
    (net (code "62") (name "MP3RIGHTOUT") (class "Default")
      (node (ref "C33") (pin "1") (pinfunction "1_1") (pintype "passive"))
      (node (ref "R26") (pin "2") (pinfunction "2_2") (pintype "passive"))
      (node (ref "R59") (pin "2") (pinfunction "2_2") (pintype "passive"))
      (node (ref "U4") (pin "39") (pinfunction "RIGHT_39") (pintype "bidirectional"))
    )
    (net (code "63") (name "MP3_CS") (class "Default")
      (node (ref "U3") (pin "84") (pinfunction "PK5(ADC13/PCINT21)_84") (pintype "bidirectional"))
      (node (ref "U4") (pin "23") (pinfunction "XCS_23") (pintype "bidirectional"))
    )
    (net (code "64") (name "MP3_DCS") (class "Default")
      (node (ref "U3") (pin "83") (pinfunction "PK6(ADC14/PCINT22)_83") (pintype "bidirectional"))
      (node (ref "U4") (pin "13") (pinfunction "XDCS/BSYNC_13") (pintype "bidirectional"))
    )
    (net (code "65") (name "MP3_DREQ") (class "Default")
      (node (ref "U3") (pin "85") (pinfunction "PK4(ADC12/PCINT20)_85") (pintype "bidirectional"))
      (node (ref "U4") (pin "8") (pinfunction "DREQ_8") (pintype "bidirectional"))
    )
    (net (code "66") (name "MP3_RST") (class "Default")
      (node (ref "R20") (pin "2") (pinfunction "2_2") (pintype "passive"))
      (node (ref "U3") (pin "86") (pinfunction "PK3(ADC11/PCINT19)_86") (pintype "bidirectional"))
      (node (ref "U4") (pin "3") (pinfunction "XRESET_3") (pintype "bidirectional"))
    )
    (net (code "67") (name "Net-(C13-Pad1)") (class "Default")
      (node (ref "C13") (pin "1") (pinfunction "1_1") (pintype "passive"))
      (node (ref "R21") (pin "1") (pinfunction "1_1") (pintype "passive"))
    )
    (net (code "68") (name "Net-(C21-Pad1)") (class "Default")
      (node (ref "C21") (pin "1") (pinfunction "1_1") (pintype "passive"))
      (node (ref "R25") (pin "1") (pinfunction "1_1") (pintype "passive"))
    )
    (net (code "69") (name "Net-(C23-Pad1)") (class "Default")
      (node (ref "C23") (pin "1") (pinfunction "1_1") (pintype "passive"))
      (node (ref "R26") (pin "1") (pinfunction "1_1") (pintype "passive"))
    )
    (net (code "70") (name "Net-(C33-Pad2)") (class "Default")
      (node (ref "C33") (pin "2") (pinfunction "2_2") (pintype "passive"))
      (node (ref "R39") (pin "2") (pinfunction "2_2") (pintype "passive"))
    )
    (net (code "71") (name "Net-(C45-Pad2)") (class "Default")
      (node (ref "C45") (pin "2") (pinfunction "2_2") (pintype "passive"))
      (node (ref "R51") (pin "2") (pinfunction "2_2") (pintype "passive"))
    )
    (net (code "72") (name "Net-(C46-Pad2)") (class "Default")
      (node (ref "C46") (pin "2") (pinfunction "2_2") (pintype "passive"))
      (node (ref "R52") (pin "2") (pinfunction "2_2") (pintype "passive"))
    )
    (net (code "73") (name "Net-(C48-Pad2)") (class "Default")
      (node (ref "C48") (pin "2") (pinfunction "2_2") (pintype "passive"))
      (node (ref "R56") (pin "2") (pinfunction "2_2") (pintype "passive"))
    )
    (net (code "74") (name "Net-(C49-Pad2)") (class "Default")
      (node (ref "C49") (pin "2") (pinfunction "2_2") (pintype "passive"))
      (node (ref "R55") (pin "1") (pinfunction "1_1") (pintype "passive"))
    )
    (net (code "75") (name "Net-(C50-Pad2)") (class "Default")
      (node (ref "C50") (pin "2") (pinfunction "2_2") (pintype "passive"))
      (node (ref "R46") (pin "1") (pinfunction "1_1") (pintype "passive"))
    )
    (net (code "76") (name "Net-(CN10-Pad3)") (class "Default")
      (node (ref "CN10") (pin "3") (pinfunction "3_3") (pintype "passive"))
      (node (ref "CN8") (pin "2") (pinfunction "2_2") (pintype "passive"))
    )
    (net (code "77") (name "Net-(CN12-Pad3)") (class "Default")
      (node (ref "CN12") (pin "3") (pinfunction "3_3") (pintype "passive"))
      (node (ref "CN9") (pin "2") (pinfunction "2_2") (pintype "passive"))
    )
    (net (code "78") (name "Net-(CN12-Pad4)") (class "Default")
      (node (ref "CN12") (pin "4") (pinfunction "4_4") (pintype "passive"))
      (node (ref "CN9") (pin "3") (pinfunction "3_3") (pintype "passive"))
    )
    (net (code "79") (name "Net-(D1-PadA)") (class "Default")
      (node (ref "D1") (pin "A") (pinfunction "A_A") (pintype "passive"))
      (node (ref "R10") (pin "1") (pinfunction "1_1") (pintype "passive"))
      (node (ref "R9") (pin "2") (pinfunction "2_2") (pintype "passive"))
      (node (ref "S101") (pin "2") (pinfunction "2_2") (pintype "passive"))
    )
    (net (code "80") (name "Net-(L1-1)") (class "Default")
      (node (ref "L1") (pin "P$1") (pinfunction "1_P$1") (pintype "passive"))
      (node (ref "U1") (pin "3") (pinfunction "L_3") (pintype "passive"))
    )
    (net (code "81") (name "Net-(L1-2)") (class "Default")
      (node (ref "C1") (pin "1") (pinfunction "1_1") (pintype "passive"))
      (node (ref "C2") (pin "1") (pinfunction "1_1") (pintype "passive"))
      (node (ref "CN1") (pin "1") (pinfunction "1_1") (pintype "passive"))
      (node (ref "L1") (pin "P$2") (pinfunction "2_P$2") (pintype "passive"))
      (node (ref "Q1") (pin "4") (pinfunction "E_4") (pintype "passive"))
      (node (ref "R3") (pin "2") (pinfunction "2_2") (pintype "passive"))
      (node (ref "R6") (pin "2") (pinfunction "2_2") (pintype "passive"))
      (node (ref "S101") (pin "4") (pinfunction "4_4") (pintype "passive"))
      (node (ref "U1") (pin "5") (pinfunction "VIN_5") (pintype "power_in"))
    )
    (net (code "82") (name "Net-(LD1-PadC)") (class "Default")
      (node (ref "LD1") (pin "C") (pinfunction "C_C") (pintype "passive"))
      (node (ref "R5") (pin "1") (pinfunction "1_1") (pintype "passive"))
    )
    (net (code "83") (name "Net-(LD2-PadC)") (class "Default")
      (node (ref "LD2") (pin "C") (pinfunction "C_C") (pintype "passive"))
      (node (ref "R8") (pin "1") (pinfunction "1_1") (pintype "passive"))
    )
    (net (code "84") (name "Net-(LD3-PadA)") (class "Default")
      (node (ref "LD3") (pin "A") (pinfunction "A_A") (pintype "passive"))
      (node (ref "R27") (pin "1") (pinfunction "1_1") (pintype "passive"))
    )
    (net (code "85") (name "Net-(LD100-PadC)") (class "Default")
      (node (ref "LD100") (pin "C") (pinfunction "C_C") (pintype "passive"))
      (node (ref "R100") (pin "1") (pinfunction "1_1") (pintype "passive"))
    )
    (net (code "86") (name "Net-(LD101-PadC)") (class "Default")
      (node (ref "LD101") (pin "C") (pinfunction "C_C") (pintype "passive"))
      (node (ref "R101") (pin "1") (pinfunction "1_1") (pintype "passive"))
    )
    (net (code "87") (name "Net-(LD102-PadA)") (class "Default")
      (node (ref "LD102") (pin "A") (pinfunction "A_A") (pintype "passive"))
      (node (ref "R12") (pin "1") (pinfunction "1_1") (pintype "passive"))
    )
    (net (code "88") (name "Net-(LD103-PadC)") (class "Default")
      (node (ref "LD103") (pin "C") (pinfunction "C_C") (pintype "passive"))
      (node (ref "R105") (pin "1") (pinfunction "1_1") (pintype "passive"))
    )
    (net (code "89") (name "Net-(LD104-PadC)") (class "Default")
      (node (ref "LD104") (pin "C") (pinfunction "C_C") (pintype "passive"))
      (node (ref "R106") (pin "1") (pinfunction "1_1") (pintype "passive"))
    )
    (net (code "90") (name "Net-(LD105-PadC)") (class "Default")
      (node (ref "LD105") (pin "C") (pinfunction "C_C") (pintype "passive"))
      (node (ref "R108") (pin "1") (pinfunction "1_1") (pintype "passive"))
    )
    (net (code "91") (name "Net-(LD106-PadC)") (class "Default")
      (node (ref "LD106") (pin "C") (pinfunction "C_C") (pintype "passive"))
      (node (ref "R109") (pin "1") (pinfunction "1_1") (pintype "passive"))
    )
    (net (code "92") (name "Net-(LD107-PadC)") (class "Default")
      (node (ref "LD107") (pin "C") (pinfunction "C_C") (pintype "passive"))
      (node (ref "R112") (pin "1") (pinfunction "1_1") (pintype "passive"))
    )
    (net (code "93") (name "Net-(LD108-PadC)") (class "Default")
      (node (ref "LD108") (pin "C") (pinfunction "C_C") (pintype "passive"))
      (node (ref "R113") (pin "1") (pinfunction "1_1") (pintype "passive"))
    )
    (net (code "94") (name "Net-(LD109-PadC)") (class "Default")
      (node (ref "LD109") (pin "C") (pinfunction "C_C") (pintype "passive"))
      (node (ref "R119") (pin "1") (pinfunction "1_1") (pintype "passive"))
    )
    (net (code "95") (name "Net-(LD110-PadC)") (class "Default")
      (node (ref "LD110") (pin "C") (pinfunction "C_C") (pintype "passive"))
      (node (ref "R120") (pin "1") (pinfunction "1_1") (pintype "passive"))
    )
    (net (code "96") (name "Net-(LD111-PadC)") (class "Default")
      (node (ref "LD111") (pin "C") (pinfunction "C_C") (pintype "passive"))
      (node (ref "R121") (pin "1") (pinfunction "1_1") (pintype "passive"))
    )
    (net (code "97") (name "Net-(LD112-PadC)") (class "Default")
      (node (ref "LD112") (pin "C") (pinfunction "C_C") (pintype "passive"))
      (node (ref "R122") (pin "1") (pinfunction "1_1") (pintype "passive"))
    )
    (net (code "98") (name "Net-(LD113-PadC)") (class "Default")
      (node (ref "LD113") (pin "C") (pinfunction "C_C") (pintype "passive"))
      (node (ref "R123") (pin "1") (pinfunction "1_1") (pintype "passive"))
    )
    (net (code "99") (name "Net-(LD114-PadC)") (class "Default")
      (node (ref "LD114") (pin "C") (pinfunction "C_C") (pintype "passive"))
      (node (ref "R124") (pin "1") (pinfunction "1_1") (pintype "passive"))
    )
    (net (code "100") (name "Net-(LD115-PadC)") (class "Default")
      (node (ref "LD115") (pin "C") (pinfunction "C_C") (pintype "passive"))
      (node (ref "R125") (pin "1") (pinfunction "1_1") (pintype "passive"))
    )
    (net (code "101") (name "Net-(LD116-PadC)") (class "Default")
      (node (ref "LD116") (pin "C") (pinfunction "C_C") (pintype "passive"))
      (node (ref "R126") (pin "1") (pinfunction "1_1") (pintype "passive"))
    )
    (net (code "102") (name "Net-(LD117-PadC)") (class "Default")
      (node (ref "LD117") (pin "C") (pinfunction "C_C") (pintype "passive"))
      (node (ref "R127") (pin "1") (pinfunction "1_1") (pintype "passive"))
    )
    (net (code "103") (name "Net-(LD118-PadC)") (class "Default")
      (node (ref "LD118") (pin "C") (pinfunction "C_C") (pintype "passive"))
      (node (ref "R128") (pin "1") (pinfunction "1_1") (pintype "passive"))
    )
    (net (code "104") (name "Net-(LD119-PadC)") (class "Default")
      (node (ref "LD119") (pin "C") (pinfunction "C_C") (pintype "passive"))
      (node (ref "R129") (pin "1") (pinfunction "1_1") (pintype "passive"))
    )
    (net (code "105") (name "Net-(LD120-PadC)") (class "Default")
      (node (ref "LD120") (pin "C") (pinfunction "C_C") (pintype "passive"))
      (node (ref "R116") (pin "1") (pinfunction "1_1") (pintype "passive"))
    )
    (net (code "106") (name "Net-(LD121-PadC)") (class "Default")
      (node (ref "LD121") (pin "C") (pinfunction "C_C") (pintype "passive"))
      (node (ref "R117") (pin "1") (pinfunction "1_1") (pintype "passive"))
    )
    (net (code "107") (name "Net-(LD122-PadC)") (class "Default")
      (node (ref "LD122") (pin "C") (pinfunction "C_C") (pintype "passive"))
      (node (ref "R118") (pin "1") (pinfunction "1_1") (pintype "passive"))
    )
    (net (code "108") (name "Net-(Q1A-B)") (class "Default")
      (node (ref "Q1") (pin "5") (pinfunction "B_5") (pintype "passive"))
      (node (ref "Q1") (pin "6") (pinfunction "C_6") (pintype "passive"))
    )
    (net (code "109") (name "Net-(Q1A-C)") (class "Default")
      (node (ref "D1") (pin "C") (pinfunction "C_C") (pintype "passive"))
      (node (ref "Q1") (pin "3") (pinfunction "C_3") (pintype "passive"))
      (node (ref "R7") (pin "2") (pinfunction "2_2") (pintype "passive"))
      (node (ref "U1") (pin "6") (pinfunction "EN_6") (pintype "input"))
    )
    (net (code "110") (name "Net-(Q2-PadB)") (class "Default")
      (node (ref "Q2") (pin "B") (pinfunction "B_B") (pintype "passive"))
      (node (ref "R10") (pin "2") (pinfunction "2_2") (pintype "passive"))
    )
    (net (code "111") (name "Net-(R38-Pad1)") (class "Default")
      (node (ref "R38") (pin "1") (pinfunction "1_1") (pintype "passive"))
      (node (ref "U9") (pin "3") (pinfunction "RG_3") (pintype "passive"))
    )
    (net (code "112") (name "Net-(R38-Pad2)") (class "Default")
      (node (ref "R38") (pin "2") (pinfunction "2_2") (pintype "passive"))
      (node (ref "U9") (pin "2") (pinfunction "RG_2") (pintype "passive"))
    )
    (net (code "113") (name "Net-(R61-Pad1)") (class "Default")
      (node (ref "R61") (pin "1") (pinfunction "1_1") (pintype "passive"))
      (node (ref "U12") (pin "3") (pinfunction "RG_3") (pintype "passive"))
    )
    (net (code "114") (name "Net-(R61-Pad2)") (class "Default")
      (node (ref "R61") (pin "2") (pinfunction "2_2") (pintype "passive"))
      (node (ref "U12") (pin "2") (pinfunction "RG_2") (pintype "passive"))
    )
    (net (code "115") (name "Net-(U1-FB)") (class "Default")
      (node (ref "R11") (pin "1") (pinfunction "1_1") (pintype "passive"))
      (node (ref "R13") (pin "2") (pinfunction "2_2") (pintype "passive"))
      (node (ref "U1") (pin "10") (pinfunction "FB_10") (pintype "passive"))
    )
    (net (code "116") (name "Net-(U1-UVLO)") (class "Default")
      (node (ref "C1") (pin "2") (pinfunction "2_2") (pintype "passive"))
      (node (ref "R2") (pin "2") (pinfunction "2_2") (pintype "passive"))
      (node (ref "R6") (pin "1") (pinfunction "1_1") (pintype "passive"))
      (node (ref "U1") (pin "7") (pinfunction "UVLO_7") (pintype "passive"))
    )
    (net (code "117") (name "Net-(U1-VAUX)") (class "Default")
      (node (ref "C3") (pin "1") (pinfunction "1_1") (pintype "passive"))
      (node (ref "U1") (pin "1") (pinfunction "VAUX_1") (pintype "passive"))
    )
    (net (code "118") (name "Net-(U2-PIO2)") (class "Default")
      (node (ref "LD2") (pin "A") (pinfunction "A_A") (pintype "passive"))
      (node (ref "U2") (pin "19") (pinfunction "PIO2_19") (pintype "bidirectional"))
    )
    (net (code "119") (name "Net-(U2-PIO5)") (class "Default")
      (node (ref "LD1") (pin "A") (pinfunction "A_A") (pintype "passive"))
      (node (ref "U2") (pin "21") (pinfunction "PIO5_21") (pintype "bidirectional"))
    )
    (net (code "120") (name "Net-(U4-GPIO2{slash}DCLK)") (class "Default")
      (node (ref "R19") (pin "2") (pinfunction "2_2") (pintype "passive"))
      (node (ref "U4") (pin "10") (pinfunction "GPIO3/SDATA_10") (pintype "bidirectional"))
      (node (ref "U4") (pin "11") (pinfunction "GPIO6_11") (pintype "bidirectional"))
      (node (ref "U4") (pin "12") (pinfunction "GPIO7_12") (pintype "bidirectional"))
      (node (ref "U4") (pin "9") (pinfunction "GPIO2/DCLK_9") (pintype "bidirectional"))
    )
    (net (code "121") (name "Net-(U4-GPIO4{slash}I2S_LROUT)") (class "Default")
      (node (ref "R33") (pin "2") (pinfunction "2_2") (pintype "passive"))
      (node (ref "U4") (pin "36") (pinfunction "GPIO4/I2S_LROUT_36") (pintype "bidirectional"))
    )
    (net (code "122") (name "Net-(U4-GPIO5{slash}I2C_MCLK)") (class "Default")
      (node (ref "R29") (pin "2") (pinfunction "2_2") (pintype "passive"))
      (node (ref "U4") (pin "25") (pinfunction "GPIO5/I2C_MCLK_25") (pintype "bidirectional"))
    )
    (net (code "123") (name "Net-(U4-LINEIN)") (class "Default")
      (node (ref "R55") (pin "2") (pinfunction "2_2") (pintype "passive"))
      (node (ref "U4") (pin "48") (pinfunction "LINEIN_48") (pintype "bidirectional"))
    )
    (net (code "124") (name "Net-(U4-MICP)") (class "Default")
      (node (ref "R46") (pin "2") (pinfunction "2_2") (pintype "passive"))
      (node (ref "U4") (pin "1") (pinfunction "MICP_1") (pintype "bidirectional"))
    )
    (net (code "125") (name "Net-(U4-RCAP)") (class "Default")
      (node (ref "C17") (pin "2") (pinfunction "2_2") (pintype "passive"))
      (node (ref "U4") (pin "44") (pinfunction "RCAP_44") (pintype "bidirectional"))
    )
    (net (code "126") (name "Net-(U4-XTAL1{slash}MCLK)") (class "Default")
      (node (ref "C22") (pin "2") (pinfunction "2_2") (pintype "passive"))
      (node (ref "R24") (pin "2") (pinfunction "2_2") (pintype "passive"))
      (node (ref "U4") (pin "18") (pinfunction "XTAL1/MCLK_18") (pintype "bidirectional"))
      (node (ref "X3") (pin "3") (pinfunction "2_3") (pintype "passive"))
      (node (ref "X4") (pin "2") (pinfunction "2_2") (pintype "passive"))
    )
    (net (code "127") (name "Net-(U4-XTAL2)") (class "Default")
      (node (ref "C14") (pin "2") (pinfunction "2_2") (pintype "passive"))
      (node (ref "R24") (pin "1") (pinfunction "1_1") (pintype "passive"))
      (node (ref "U4") (pin "17") (pinfunction "XTAL2_17") (pintype "bidirectional"))
      (node (ref "X3") (pin "1") (pinfunction "1_1") (pintype "passive"))
      (node (ref "X4") (pin "1") (pinfunction "1_1") (pintype "passive"))
    )
    (net (code "128") (name "Net-(U6-CH0)") (class "Default")
      (node (ref "C47") (pin "1") (pinfunction "1_1") (pintype "passive"))
      (node (ref "R54") (pin "2") (pinfunction "2_2") (pintype "passive"))
      (node (ref "U6") (pin "2") (pinfunction "CH0_2") (pintype "passive"))
    )
    (net (code "129") (name "Net-(U6-VOUT)") (class "Default")
      (node (ref "R34") (pin "2") (pinfunction "2_2") (pintype "passive"))
      (node (ref "U6") (pin "1") (pinfunction "VOUT_1") (pintype "passive"))
    )
    (net (code "130") (name "Net-(U7-W)") (class "Default")
      (node (ref "R35") (pin "1") (pinfunction "1_1") (pintype "passive"))
      (node (ref "R36") (pin "2") (pinfunction "2_2") (pintype "passive"))
      (node (ref "R37") (pin "2") (pinfunction "2_2") (pintype "passive"))
      (node (ref "U7") (pin "5") (pinfunction "W_5") (pintype "passive"))
    )
    (net (code "131") (name "Net-(U8-W)") (class "Default")
      (node (ref "R43") (pin "2") (pinfunction "2_2") (pintype "passive"))
      (node (ref "R44") (pin "2") (pinfunction "2_2") (pintype "passive"))
      (node (ref "R48") (pin "1") (pinfunction "1_1") (pintype "passive"))
      (node (ref "U8") (pin "5") (pinfunction "W_5") (pintype "passive"))
    )
    (net (code "132") (name "Net-(U9-+IN)") (class "Default")
      (node (ref "C30") (pin "2") (pinfunction "2_2") (pintype "passive"))
      (node (ref "C36") (pin "2") (pinfunction "2_2") (pintype "passive"))
      (node (ref "R36") (pin "1") (pinfunction "1_1") (pintype "passive"))
      (node (ref "U9") (pin "4") (pinfunction "+IN_4") (pintype "input"))
    )
    (net (code "133") (name "Net-(U9--IN)") (class "Default")
      (node (ref "C36") (pin "1") (pinfunction "1_1") (pintype "passive"))
      (node (ref "C43") (pin "1") (pinfunction "1_1") (pintype "passive"))
      (node (ref "R50") (pin "2") (pinfunction "2_2") (pintype "passive"))
      (node (ref "U9") (pin "1") (pinfunction "-IN_1") (pintype "input"))
    )
    (net (code "134") (name "Net-(U9-OUT)") (class "Default")
      (node (ref "R42") (pin "1") (pinfunction "1_1") (pintype "passive"))
      (node (ref "U9") (pin "7") (pinfunction "OUT_7") (pintype "output"))
    )
    (net (code "135") (name "Net-(U9-REF)") (class "Default")
      (node (ref "R40") (pin "2") (pinfunction "2_2") (pintype "passive"))
      (node (ref "U9") (pin "6") (pinfunction "REF_6") (pintype "passive"))
    )
    (net (code "136") (name "Net-(U10-CH0)") (class "Default")
      (node (ref "C35") (pin "1") (pinfunction "1_1") (pintype "passive"))
      (node (ref "R42") (pin "2") (pinfunction "2_2") (pintype "passive"))
      (node (ref "U10") (pin "2") (pinfunction "CH0_2") (pintype "passive"))
    )
    (net (code "137") (name "Net-(U10-VOUT)") (class "Default")
      (node (ref "R49") (pin "2") (pinfunction "2_2") (pintype "passive"))
      (node (ref "U10") (pin "1") (pinfunction "VOUT_1") (pintype "passive"))
    )
    (net (code "138") (name "Net-(U11-BYPASS)") (class "Default")
      (node (ref "C34") (pin "1") (pinfunction "1_1") (pintype "passive"))
      (node (ref "U11") (pin "1") (pinfunction "BYPASS_1") (pintype "passive"))
    )
    (net (code "139") (name "Net-(U11-IN1-)") (class "Default")
      (node (ref "R52") (pin "1") (pinfunction "1_1") (pintype "passive"))
      (node (ref "R56") (pin "1") (pinfunction "1_1") (pintype "passive"))
      (node (ref "R57") (pin "1") (pinfunction "1_1") (pintype "passive"))
      (node (ref "R58") (pin "2") (pinfunction "2_2") (pintype "passive"))
      (node (ref "U11") (pin "8") (pinfunction "IN1-_8") (pintype "passive"))
    )
    (net (code "140") (name "Net-(U11-IN2-)") (class "Default")
      (node (ref "R39") (pin "1") (pinfunction "1_1") (pintype "passive"))
      (node (ref "R41") (pin "1") (pinfunction "1_1") (pintype "passive"))
      (node (ref "R47") (pin "2") (pinfunction "2_2") (pintype "passive"))
      (node (ref "R51") (pin "1") (pinfunction "1_1") (pintype "passive"))
      (node (ref "U11") (pin "4") (pinfunction "IN2-_4") (pintype "passive"))
    )
    (net (code "141") (name "Net-(U11-V02)") (class "Default")
      (node (ref "C40") (pin "+") (pinfunction "+_+") (pintype "passive"))
      (node (ref "R47") (pin "1") (pinfunction "1_1") (pintype "passive"))
      (node (ref "U11") (pin "5") (pinfunction "V02_5") (pintype "passive"))
    )
    (net (code "142") (name "Net-(U11-VO1)") (class "Default")
      (node (ref "C41") (pin "+") (pinfunction "+_+") (pintype "passive"))
      (node (ref "R58") (pin "1") (pinfunction "1_1") (pintype "passive"))
      (node (ref "U11") (pin "7") (pinfunction "VO1_7") (pintype "passive"))
    )
    (net (code "143") (name "Net-(U12-+IN)") (class "Default")
      (node (ref "C37") (pin "2") (pinfunction "2_2") (pintype "passive"))
      (node (ref "C38") (pin "2") (pinfunction "2_2") (pintype "passive"))
      (node (ref "R44") (pin "1") (pinfunction "1_1") (pintype "passive"))
      (node (ref "U12") (pin "4") (pinfunction "+IN_4") (pintype "input"))
    )
    (net (code "144") (name "Net-(U12--IN)") (class "Default")
      (node (ref "C38") (pin "1") (pinfunction "1_1") (pintype "passive"))
      (node (ref "C52") (pin "1") (pinfunction "1_1") (pintype "passive"))
      (node (ref "R63") (pin "2") (pinfunction "2_2") (pintype "passive"))
      (node (ref "U12") (pin "1") (pinfunction "-IN_1") (pintype "input"))
    )
    (net (code "145") (name "Net-(U12-OUT)") (class "Default")
      (node (ref "R54") (pin "1") (pinfunction "1_1") (pintype "passive"))
      (node (ref "U12") (pin "7") (pinfunction "OUT_7") (pintype "output"))
    )
    (net (code "146") (name "Net-(U12-REF)") (class "Default")
      (node (ref "R53") (pin "2") (pinfunction "2_2") (pintype "passive"))
      (node (ref "U12") (pin "6") (pinfunction "REF_6") (pintype "passive"))
    )
    (net (code "147") (name "PIO4") (class "Default")
      (node (ref "R1") (pin "2") (pinfunction "2_2") (pintype "passive"))
      (node (ref "TP1") (pin "P$1") (pinfunction "1_P$1") (pintype "bidirectional"))
      (node (ref "U2") (pin "22") (pinfunction "PIO4_22") (pintype "bidirectional"))
    )
    (net (code "148") (name "PS_MODE") (class "Default")
      (node (ref "U1") (pin "8") (pinfunction "PS_8") (pintype "input"))
      (node (ref "U3") (pin "55") (pinfunction "(A10)PC2_55") (pintype "bidirectional"))
    )
    (net (code "149") (name "P_ONOFF_CTRL") (class "Default")
      (node (ref "Q1") (pin "2") (pinfunction "B_2") (pintype "passive"))
      (node (ref "U3") (pin "54") (pinfunction "(A9)PC1_54") (pintype "bidirectional"))
    )
    (net (code "150") (name "RESET") (class "Default")
      (node (ref "C5") (pin "1") (pinfunction "1_1") (pintype "passive"))
      (node (ref "C6") (pin "2") (pinfunction "2_2") (pintype "passive"))
      (node (ref "CN4") (pin "5") (pinfunction "5_5") (pintype "passive"))
      (node (ref "R16") (pin "2") (pinfunction "2_2") (pintype "passive"))
      (node (ref "TP11") (pin "1") (pinfunction "1_1") (pintype "passive"))
      (node (ref "U3") (pin "30") (pinfunction "RESET_30") (pintype "input"))
    )
    (net (code "151") (name "RIGHTIN") (class "Default")
      (node (ref "C45") (pin "1") (pinfunction "1_1") (pintype "passive"))
      (node (ref "C49") (pin "1") (pinfunction "1_1") (pintype "passive"))
      (node (ref "CN11") (pin "2") (pinfunction "2_2") (pintype "passive"))
      (node (ref "Z1") (pin "1") (pinfunction "1_1") (pintype "passive"))
    )
    (net (code "152") (name "RIGHTOUT") (class "Default")
      (node (ref "C40") (pin "-") (pinfunction "-_-") (pintype "passive"))
      (node (ref "CN12") (pin "2") (pinfunction "2_2") (pintype "passive"))
      (node (ref "R59") (pin "1") (pinfunction "1_1") (pintype "passive"))
      (node (ref "Z3") (pin "1") (pinfunction "1_1") (pintype "passive"))
    )
    (net (code "153") (name "SCK") (class "Default")
      (node (ref "CN2") (pin "5") (pinfunction "SCK_5") (pintype "bidirectional"))
      (node (ref "CN4") (pin "3") (pinfunction "3_3") (pintype "passive"))
      (node (ref "TP6") (pin "1") (pinfunction "1_1") (pintype "passive"))
      (node (ref "U10") (pin "7") (pinfunction "SCK_7") (pintype "input"))
      (node (ref "U3") (pin "20") (pinfunction "(SCK/PCINT1)PB1_20") (pintype "bidirectional"))
      (node (ref "U4") (pin "28") (pinfunction "SCLK_28") (pintype "bidirectional"))
      (node (ref "U6") (pin "7") (pinfunction "SCK_7") (pintype "input"))
    )
    (net (code "154") (name "SCL") (class "Default")
      (node (ref "R18") (pin "2") (pinfunction "2_2") (pintype "passive"))
      (node (ref "TP8") (pin "1") (pinfunction "1_1") (pintype "passive"))
      (node (ref "U3") (pin "43") (pinfunction "(SCL/INT0)PD0_43") (pintype "bidirectional"))
    )
    (net (code "155") (name "SDA") (class "Default")
      (node (ref "R17") (pin "2") (pinfunction "2_2") (pintype "passive"))
      (node (ref "TP10") (pin "1") (pinfunction "1_1") (pintype "passive"))
      (node (ref "U3") (pin "44") (pinfunction "(SDA/INT1)PD1_44") (pintype "bidirectional"))
    )
    (net (code "156") (name "SDCARD_CS") (class "Default")
      (node (ref "CN2") (pin "2") (pinfunction "CS_2") (pintype "bidirectional"))
      (node (ref "U3") (pin "69") (pinfunction "PJ6(PCINT15)_69") (pintype "bidirectional"))
    )
    (net (code "157") (name "TMP+") (class "Default")
      (node (ref "CN10") (pin "4") (pinfunction "4_4") (pintype "passive"))
      (node (ref "R60") (pin "2") (pinfunction "2_2") (pintype "passive"))
      (node (ref "R63") (pin "1") (pinfunction "1_1") (pintype "passive"))
    )
    (net (code "158") (name "TMPOF_CS") (class "Default")
      (node (ref "U3") (pin "27") (pinfunction "PH7(T4)_27") (pintype "bidirectional"))
      (node (ref "U8") (pin "4") (pinfunction "CS_4") (pintype "passive"))
    )
    (net (code "159") (name "TMP_CS") (class "Default")
      (node (ref "U3") (pin "28") (pinfunction "(TOSC2)PG3_28") (pintype "bidirectional"))
      (node (ref "U6") (pin "5") (pinfunction "CS_5") (pintype "input"))
    )
    (net (code "160") (name "XTAL1") (class "Default")
      (node (ref "C11") (pin "2") (pinfunction "2_2") (pintype "passive"))
      (node (ref "R22") (pin "2") (pinfunction "2_2") (pintype "passive"))
      (node (ref "R23") (pin "1") (pinfunction "1_1") (pintype "passive"))
      (node (ref "X1") (pin "3") (pinfunction "3_3") (pintype "passive"))
      (node (ref "X2") (pin "2") (pinfunction "2_2") (pintype "passive"))
    )
    (net (code "161") (name "XTAL1R") (class "Default")
      (node (ref "R22") (pin "1") (pinfunction "1_1") (pintype "passive"))
      (node (ref "U3") (pin "34") (pinfunction "XTAL1_34") (pintype "input"))
    )
    (net (code "162") (name "XTAL2") (class "Default")
      (node (ref "C19") (pin "2") (pinfunction "2_2") (pintype "passive"))
      (node (ref "R23") (pin "2") (pinfunction "2_2") (pintype "passive"))
      (node (ref "U3") (pin "33") (pinfunction "XTAL2_33") (pintype "output"))
      (node (ref "X1") (pin "1") (pinfunction "1_1") (pintype "passive"))
      (node (ref "X2") (pin "1") (pinfunction "1_1") (pintype "passive"))
    )
    (net (code "163") (name "unconnected-(CN2-NC-Pad1)") (class "Default")
      (node (ref "CN2") (pin "1") (pinfunction "NC_1") (pintype "bidirectional"))
    )
    (net (code "164") (name "unconnected-(CN2-RSV-Pad8)") (class "Default")
      (node (ref "CN2") (pin "8") (pinfunction "RSV_8") (pintype "bidirectional"))
    )
    (net (code "165") (name "unconnected-(S100-Pad1)") (class "Default")
      (node (ref "S100") (pin "1") (pinfunction "1_1") (pintype "passive"))
    )
    (net (code "166") (name "unconnected-(S100-Pad3)") (class "Default")
      (node (ref "S100") (pin "3") (pinfunction "3_3") (pintype "passive"))
    )
    (net (code "167") (name "unconnected-(S101-Pad1)") (class "Default")
      (node (ref "S101") (pin "1") (pinfunction "1_1") (pintype "passive"))
    )
    (net (code "168") (name "unconnected-(S101-Pad3)") (class "Default")
      (node (ref "S101") (pin "3") (pinfunction "3_3") (pintype "passive"))
    )
    (net (code "169") (name "unconnected-(S102-Pad1)") (class "Default")
      (node (ref "S102") (pin "1") (pinfunction "1_1") (pintype "passive"))
    )
    (net (code "170") (name "unconnected-(S102-Pad3)") (class "Default")
      (node (ref "S102") (pin "3") (pinfunction "3_3") (pintype "passive"))
    )
    (net (code "171") (name "unconnected-(S103-Pad1)") (class "Default")
      (node (ref "S103") (pin "1") (pinfunction "1_1") (pintype "passive"))
    )
    (net (code "172") (name "unconnected-(S103-Pad3)") (class "Default")
      (node (ref "S103") (pin "3") (pinfunction "3_3") (pintype "passive"))
    )
    (net (code "173") (name "unconnected-(S104-Pad1)") (class "Default")
      (node (ref "S104") (pin "1") (pinfunction "1_1") (pintype "passive"))
    )
    (net (code "174") (name "unconnected-(S104-Pad3)") (class "Default")
      (node (ref "S104") (pin "3") (pinfunction "3_3") (pintype "passive"))
    )
    (net (code "175") (name "unconnected-(S105-Pad1)") (class "Default")
      (node (ref "S105") (pin "1") (pinfunction "1_1") (pintype "passive"))
    )
    (net (code "176") (name "unconnected-(S105-Pad3)") (class "Default")
      (node (ref "S105") (pin "3") (pinfunction "3_3") (pintype "passive"))
    )
    (net (code "177") (name "unconnected-(S106-Pad1)") (class "Default")
      (node (ref "S106") (pin "1") (pinfunction "1_1") (pintype "passive"))
    )
    (net (code "178") (name "unconnected-(S106-Pad3)") (class "Default")
      (node (ref "S106") (pin "3") (pinfunction "3_3") (pintype "passive"))
    )
    (net (code "179") (name "unconnected-(S107-Pad1)") (class "Default")
      (node (ref "S107") (pin "1") (pinfunction "1_1") (pintype "passive"))
    )
    (net (code "180") (name "unconnected-(S107-Pad3)") (class "Default")
      (node (ref "S107") (pin "3") (pinfunction "3_3") (pintype "passive"))
    )
    (net (code "181") (name "unconnected-(S108-Pad1)") (class "Default")
      (node (ref "S108") (pin "1") (pinfunction "1_1") (pintype "passive"))
    )
    (net (code "182") (name "unconnected-(S108-Pad3)") (class "Default")
      (node (ref "S108") (pin "3") (pinfunction "3_3") (pintype "passive"))
    )
    (net (code "183") (name "unconnected-(U2-AIO1-Pad35)") (class "Default")
      (node (ref "U2") (pin "35") (pinfunction "AIO1_35") (pintype "bidirectional"))
    )
    (net (code "184") (name "unconnected-(U2-AIO2-Pad30)") (class "Default")
      (node (ref "U2") (pin "30") (pinfunction "AIO2_30") (pintype "bidirectional"))
    )
    (net (code "185") (name "unconnected-(U2-NC-Pad26)") (class "Default")
      (node (ref "U2") (pin "26") (pinfunction "NC_26") (pintype "bidirectional"))
    )
    (net (code "186") (name "unconnected-(U2-PCMCLK-Pad7)") (class "Default")
      (node (ref "U2") (pin "7") (pinfunction "PCMCLK_7") (pintype "bidirectional"))
    )
    (net (code "187") (name "unconnected-(U2-PCMIN-Pad9)") (class "Default")
      (node (ref "U2") (pin "9") (pinfunction "PCMIN_9") (pintype "bidirectional"))
    )
    (net (code "188") (name "unconnected-(U2-PCMOUT-Pad10)") (class "Default")
      (node (ref "U2") (pin "10") (pinfunction "PCMOUT_10") (pintype "bidirectional"))
    )
    (net (code "189") (name "unconnected-(U2-PCMSYNC-Pad8)") (class "Default")
      (node (ref "U2") (pin "8") (pinfunction "PCMSYNC_8") (pintype "bidirectional"))
    )
    (net (code "190") (name "unconnected-(U2-PIO3-Pad20)") (class "Default")
      (node (ref "U2") (pin "20") (pinfunction "PIO3_20") (pintype "bidirectional"))
    )
    (net (code "191") (name "unconnected-(U2-PIO6-Pad3)") (class "Default")
      (node (ref "U2") (pin "3") (pinfunction "PIO6_3") (pintype "bidirectional"))
    )
    (net (code "192") (name "unconnected-(U2-PIO7-Pad4)") (class "Default")
      (node (ref "U2") (pin "4") (pinfunction "PIO7_4") (pintype "bidirectional"))
    )
    (net (code "193") (name "unconnected-(U2-PIO8-Pad34)") (class "Default")
      (node (ref "U2") (pin "34") (pinfunction "PIO8_34") (pintype "bidirectional"))
    )
    (net (code "194") (name "unconnected-(U2-PIO9-Pad33)") (class "Default")
      (node (ref "U2") (pin "33") (pinfunction "PIO9_33") (pintype "bidirectional"))
    )
    (net (code "195") (name "unconnected-(U2-PIO10-Pad32)") (class "Default")
      (node (ref "U2") (pin "32") (pinfunction "PIO10_32") (pintype "bidirectional"))
    )
    (net (code "196") (name "unconnected-(U2-PIO11-Pad31)") (class "Default")
      (node (ref "U2") (pin "31") (pinfunction "PIO11_31") (pintype "bidirectional"))
    )
    (net (code "197") (name "unconnected-(U2-SPICLK-Pad6)") (class "Default")
      (node (ref "U2") (pin "6") (pinfunction "SPICLK_6") (pintype "bidirectional"))
    )
    (net (code "198") (name "unconnected-(U2-SPICSB-Pad23)") (class "Default")
      (node (ref "U2") (pin "23") (pinfunction "SPICSB_23") (pintype "bidirectional"))
    )
    (net (code "199") (name "unconnected-(U2-SPIMISO-Pad24)") (class "Default")
      (node (ref "U2") (pin "24") (pinfunction "SPIMISO_24") (pintype "bidirectional"))
    )
    (net (code "200") (name "unconnected-(U2-SPIMOSI-Pad2)") (class "Default")
      (node (ref "U2") (pin "2") (pinfunction "SPIMOSI_2") (pintype "bidirectional"))
    )
    (net (code "201") (name "unconnected-(U2-USBD+-Pad17)") (class "Default")
      (node (ref "U2") (pin "17") (pinfunction "USBD+_17") (pintype "bidirectional"))
    )
    (net (code "202") (name "unconnected-(U2-USBD--Pad18)") (class "Default")
      (node (ref "U2") (pin "18") (pinfunction "USBD-_18") (pintype "bidirectional"))
    )
    (net (code "203") (name "unconnected-(U3-(A11)PC3-Pad56)") (class "Default")
      (node (ref "U3") (pin "56") (pinfunction "(A11)PC3_56") (pintype "bidirectional"))
    )
    (net (code "204") (name "unconnected-(U3-(A12)PC4-Pad57)") (class "Default")
      (node (ref "U3") (pin "57") (pinfunction "(A12)PC4_57") (pintype "bidirectional"))
    )
    (net (code "205") (name "unconnected-(U3-(A13)PC5-Pad58)") (class "Default")
      (node (ref "U3") (pin "58") (pinfunction "(A13)PC5_58") (pintype "bidirectional"))
    )
    (net (code "206") (name "unconnected-(U3-(A14)PC6-Pad59)") (class "Default")
      (node (ref "U3") (pin "59") (pinfunction "(A14)PC6_59") (pintype "bidirectional"))
    )
    (net (code "207") (name "unconnected-(U3-(A15)PC7-Pad60)") (class "Default")
      (node (ref "U3") (pin "60") (pinfunction "(A15)PC7_60") (pintype "bidirectional"))
    )
    (net (code "208") (name "unconnected-(U3-(AD7)PA7-Pad71)") (class "Default")
      (node (ref "U3") (pin "71") (pinfunction "(AD7)PA7_71") (pintype "bidirectional"))
    )
    (net (code "209") (name "unconnected-(U3-(ADC2)PF2-Pad95)") (class "Default")
      (node (ref "U3") (pin "95") (pinfunction "(ADC2)PF2_95") (pintype "bidirectional"))
    )
    (net (code "210") (name "unconnected-(U3-(ADC3)PF3-Pad94)") (class "Default")
      (node (ref "U3") (pin "94") (pinfunction "(ADC3)PF3_94") (pintype "bidirectional"))
    )
    (net (code "211") (name "unconnected-(U3-(ADC4{slash}TCK)PF4-Pad93)") (class "Default")
      (node (ref "U3") (pin "93") (pinfunction "(ADC4/TCK)PF4_93") (pintype "bidirectional"))
    )
    (net (code "212") (name "unconnected-(U3-(ADC5{slash}TMS)PF5-Pad92)") (class "Default")
      (node (ref "U3") (pin "92") (pinfunction "(ADC5/TMS)PF5_92") (pintype "bidirectional"))
    )
    (net (code "213") (name "unconnected-(U3-(ADC6{slash}TDO)PF6-Pad91)") (class "Default")
      (node (ref "U3") (pin "91") (pinfunction "(ADC6/TDO)PF6_91") (pintype "bidirectional"))
    )
    (net (code "214") (name "unconnected-(U3-(ICP1)PD4-Pad47)") (class "Default")
      (node (ref "U3") (pin "47") (pinfunction "(ICP1)PD4_47") (pintype "bidirectional"))
    )
    (net (code "215") (name "unconnected-(U3-(RD)PG1-Pad52)") (class "Default")
      (node (ref "U3") (pin "52") (pinfunction "(RD)PG1_52") (pintype "bidirectional"))
    )
    (net (code "216") (name "unconnected-(U3-(RXD1{slash}INT2)PD2-Pad45)") (class "Default")
      (node (ref "U3") (pin "45") (pinfunction "(RXD1/INT2)PD2_45") (pintype "bidirectional"))
    )
    (net (code "217") (name "unconnected-(U3-(TOSC1)PG4-Pad29)") (class "Default")
      (node (ref "U3") (pin "29") (pinfunction "(TOSC1)PG4_29") (pintype "bidirectional"))
    )
    (net (code "218") (name "unconnected-(U3-(TXD1{slash}INT3)PD3-Pad46)") (class "Default")
      (node (ref "U3") (pin "46") (pinfunction "(TXD1/INT3)PD3_46") (pintype "bidirectional"))
    )
    (net (code "219") (name "unconnected-(U3-(WR)PG0-Pad51)") (class "Default")
      (node (ref "U3") (pin "51") (pinfunction "(WR)PG0_51") (pintype "bidirectional"))
    )
    (net (code "220") (name "unconnected-(U3-(XCK1)PD5-Pad48)") (class "Default")
      (node (ref "U3") (pin "48") (pinfunction "(XCK1)PD5_48") (pintype "bidirectional"))
    )
    (net (code "221") (name "unconnected-(U3-PJ2(XCK3{slash}PCINT11)-Pad65)") (class "Default")
      (node (ref "U3") (pin "65") (pinfunction "PJ2(XCK3/PCINT11)_65") (pintype "bidirectional"))
    )
    (net (code "222") (name "unconnected-(U3-PJ3(PCINT12)-Pad66)") (class "Default")
      (node (ref "U3") (pin "66") (pinfunction "PJ3(PCINT12)_66") (pintype "bidirectional"))
    )
    (net (code "223") (name "unconnected-(U3-PJ4(PCINT13)-Pad67)") (class "Default")
      (node (ref "U3") (pin "67") (pinfunction "PJ4(PCINT13)_67") (pintype "bidirectional"))
    )
    (net (code "224") (name "unconnected-(U3-PJ5(PCINT14)-Pad68)") (class "Default")
      (node (ref "U3") (pin "68") (pinfunction "PJ5(PCINT14)_68") (pintype "bidirectional"))
    )
    (net (code "225") (name "unconnected-(U3-PL2(T5)-Pad37)") (class "Default")
      (node (ref "U3") (pin "37") (pinfunction "PL2(T5)_37") (pintype "bidirectional"))
    )
    (net (code "226") (name "unconnected-(U3-PL6-Pad41)") (class "Default")
      (node (ref "U3") (pin "41") (pinfunction "PL6_41") (pintype "bidirectional"))
    )
    (net (code "227") (name "unconnected-(U3-PL7-Pad42)") (class "Default")
      (node (ref "U3") (pin "42") (pinfunction "PL7_42") (pintype "bidirectional"))
    )
    (net (code "228") (name "unconnected-(U4-MICN-Pad2)") (class "Default")
      (node (ref "U4") (pin "2") (pinfunction "MICN_2") (pintype "bidirectional"))
    )
    (net (code "229") (name "unconnected-(U4-VCO-Pad15)") (class "Default")
      (node (ref "U4") (pin "15") (pinfunction "VCO_15") (pintype "bidirectional"))
    )
    (net (code "230") (name "unconnected-(U5-BP-Pad4)") (class "Default")
      (node (ref "U5") (pin "4") (pinfunction "BP_4") (pintype "input"))
    )
  )
)
